# aloysius_B_v1.net
KiCad netlist of a schematic drawn in EAGLE
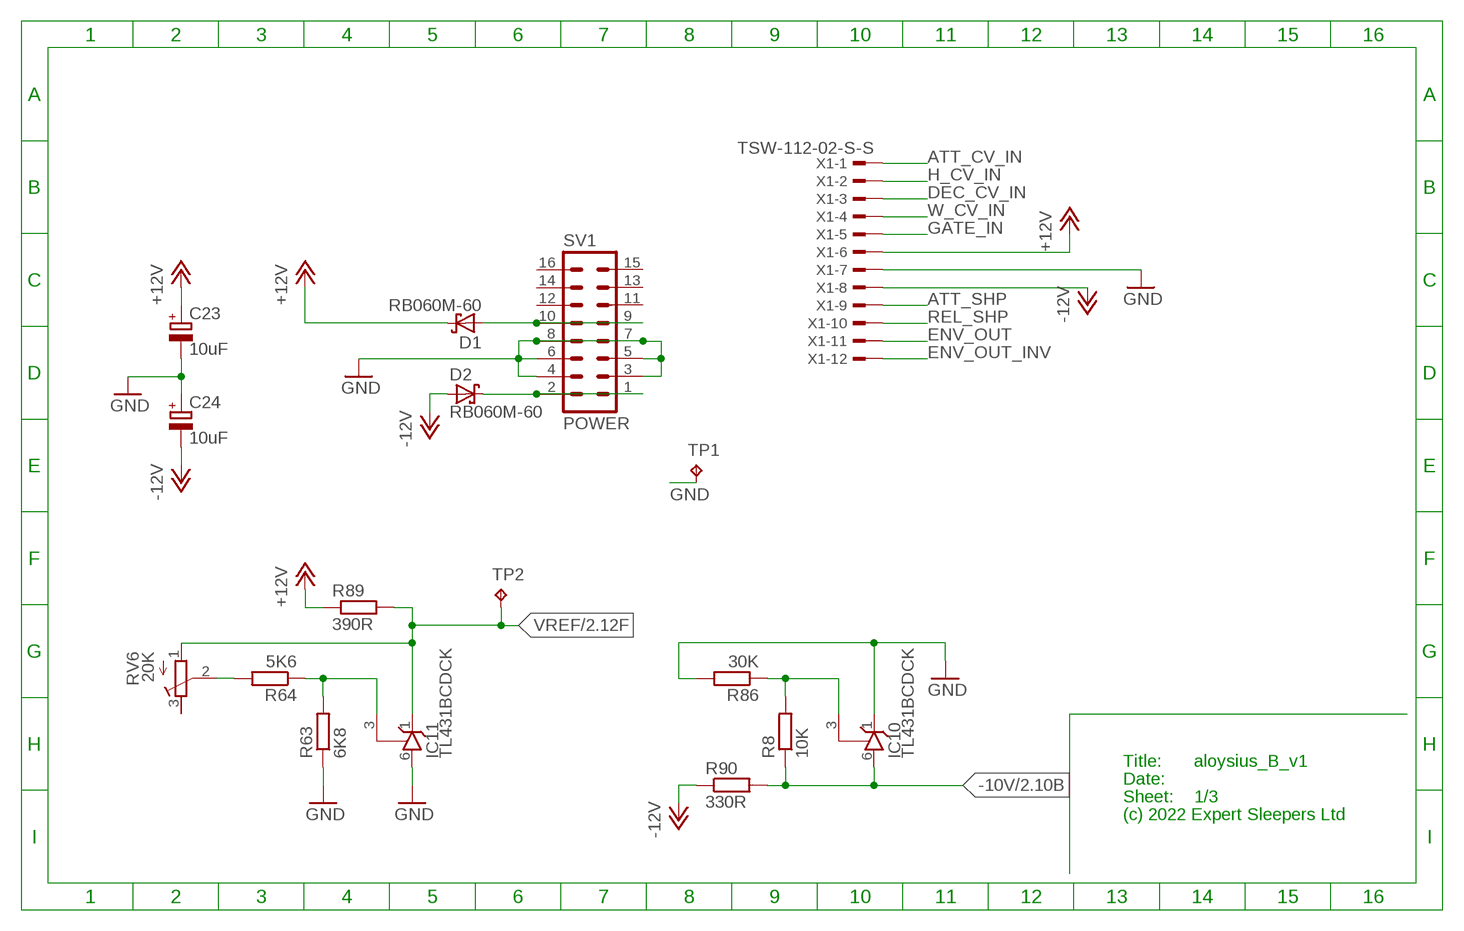
[diagram p0: schematic, sheet 1]
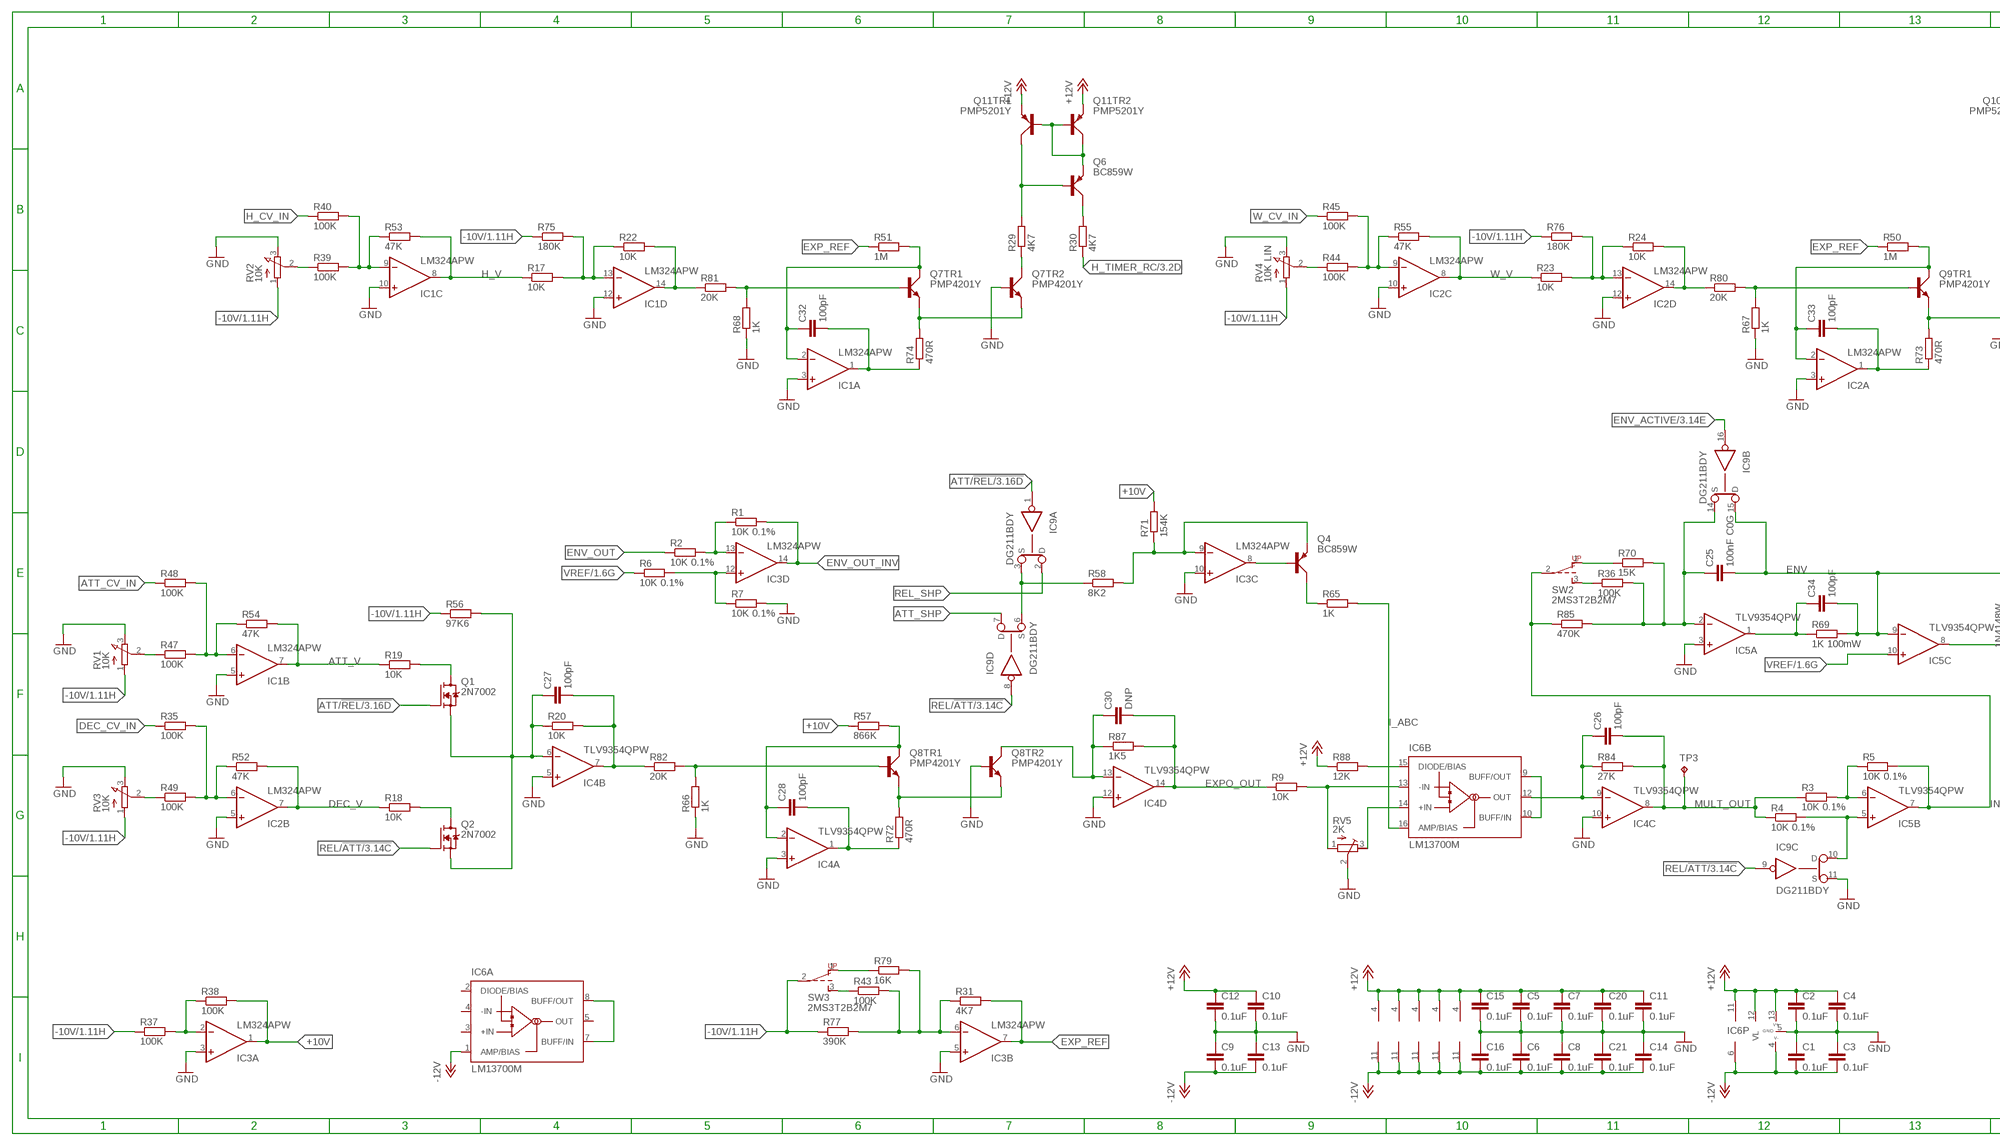
[diagram p1: schematic, sheet 2, part 1 of 2]
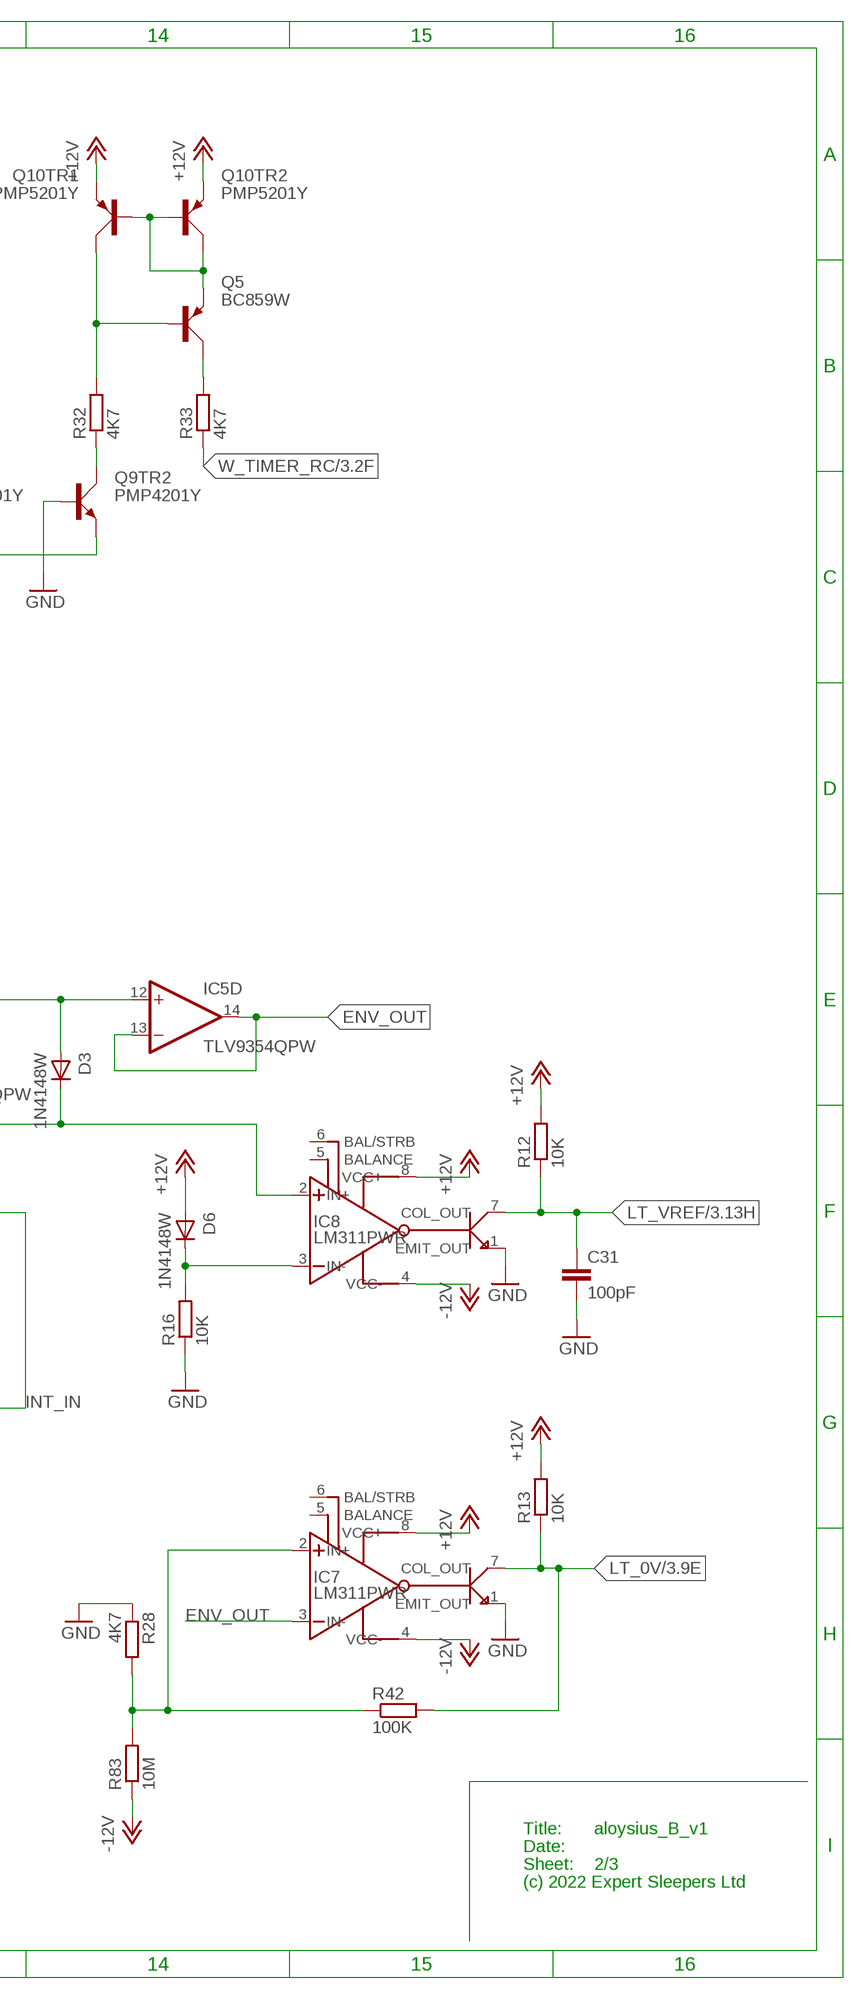
[diagram p2: schematic, sheet 2, part 2 of 2]
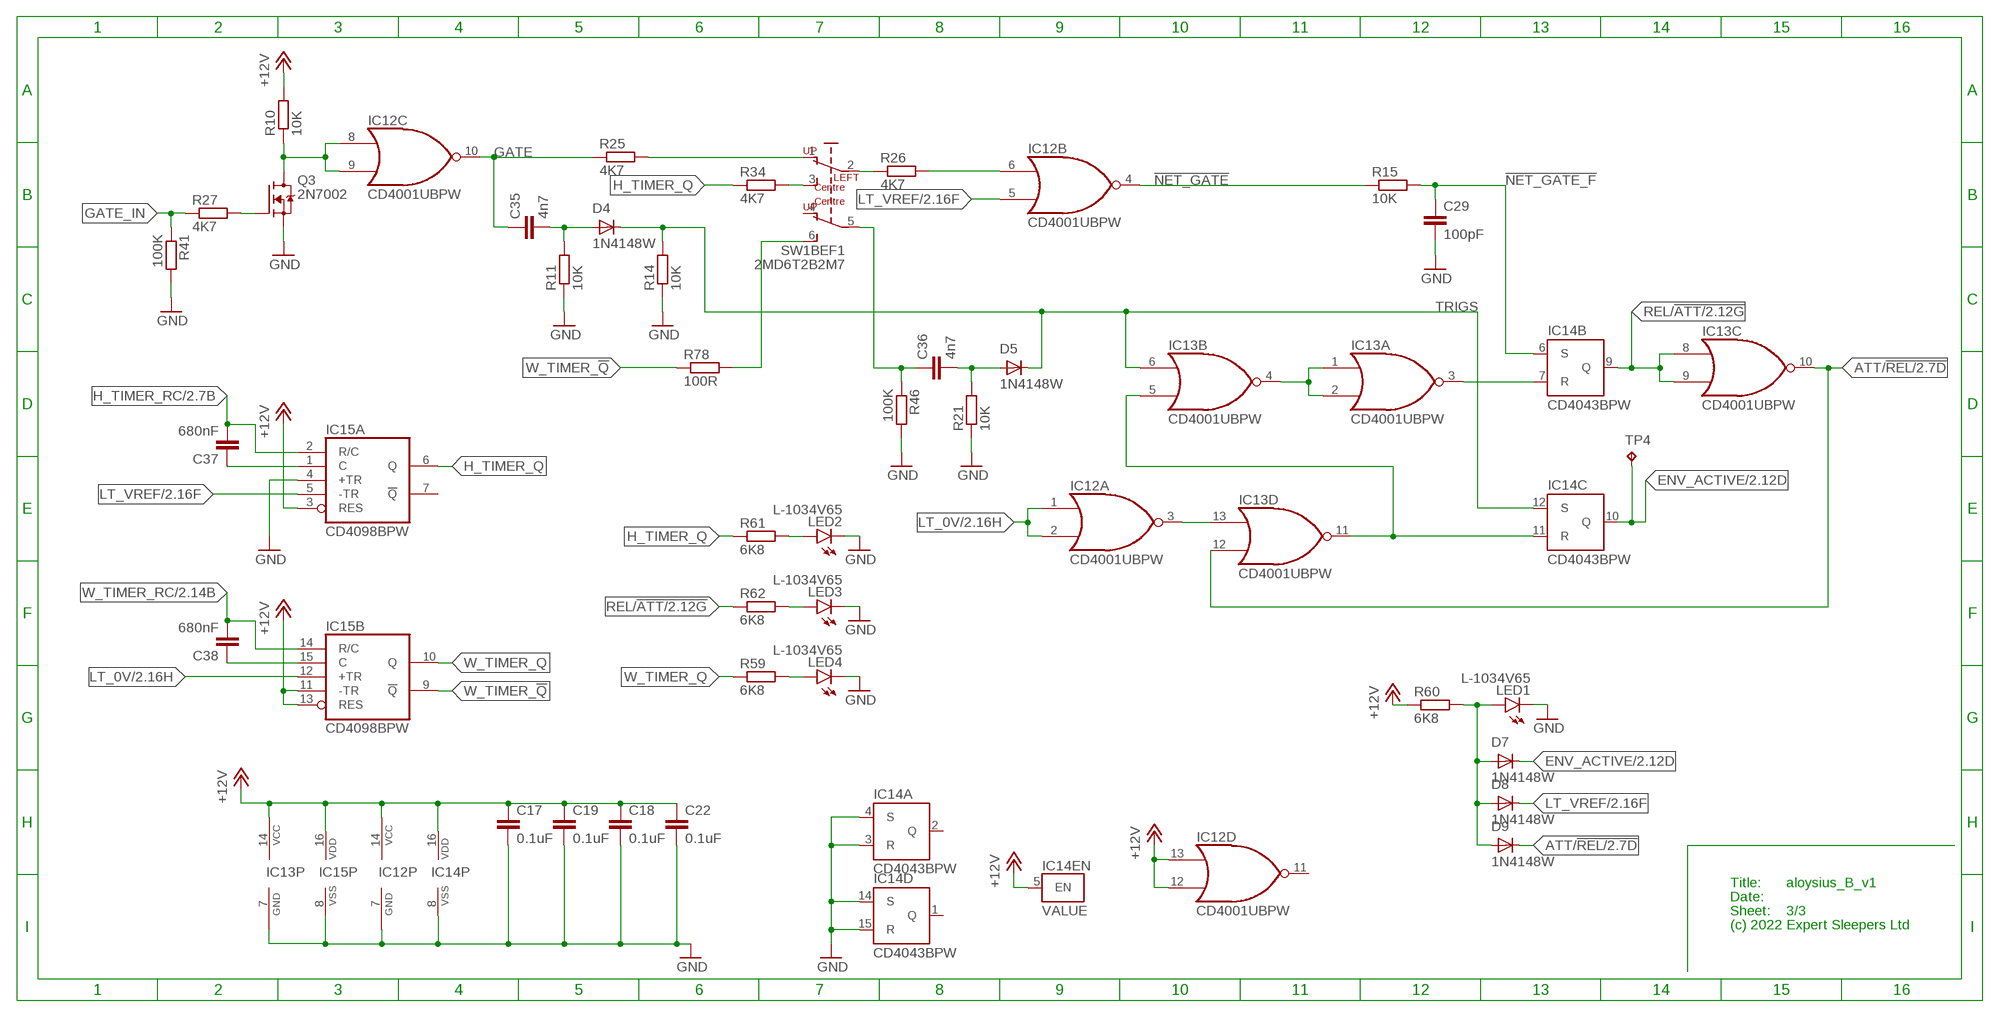
[diagram p3: schematic, sheet 3]

(export (version "E")
  (design (tool "Eeschema 10.0.6"))
  (components
    (comp (ref "C1")
      (value "0.1uF")
      (footprint "eagle-import:C0402")
      (libsource (lib "eagle-import") (part "C-EUC0402"))
    )
    (comp (ref "C2")
      (value "0.1uF")
      (footprint "eagle-import:C0402")
      (libsource (lib "eagle-import") (part "C-EUC0402"))
    )
    (comp (ref "C3")
      (value "0.1uF")
      (footprint "eagle-import:C0402")
      (libsource (lib "eagle-import") (part "C-EUC0402"))
    )
    (comp (ref "C4")
      (value "0.1uF")
      (footprint "eagle-import:C0402")
      (libsource (lib "eagle-import") (part "C-EUC0402"))
    )
    (comp (ref "C5")
      (value "0.1uF")
      (footprint "eagle-import:C0402")
      (libsource (lib "eagle-import") (part "C-EUC0402"))
    )
    (comp (ref "C6")
      (value "0.1uF")
      (footprint "eagle-import:C0402")
      (libsource (lib "eagle-import") (part "C-EUC0402"))
    )
    (comp (ref "C7")
      (value "0.1uF")
      (footprint "eagle-import:C0402")
      (libsource (lib "eagle-import") (part "C-EUC0402"))
    )
    (comp (ref "C8")
      (value "0.1uF")
      (footprint "eagle-import:C0402")
      (libsource (lib "eagle-import") (part "C-EUC0402"))
    )
    (comp (ref "C9")
      (value "0.1uF")
      (footprint "eagle-import:C0402")
      (libsource (lib "eagle-import") (part "C-EUC0402"))
    )
    (comp (ref "C10")
      (value "0.1uF")
      (footprint "eagle-import:C0402")
      (libsource (lib "eagle-import") (part "C-EUC0402"))
    )
    (comp (ref "C11")
      (value "0.1uF")
      (footprint "eagle-import:C0402")
      (libsource (lib "eagle-import") (part "C-EUC0402"))
    )
    (comp (ref "C12")
      (value "0.1uF")
      (footprint "eagle-import:C0402")
      (libsource (lib "eagle-import") (part "C-EUC0402"))
    )
    (comp (ref "C13")
      (value "0.1uF")
      (footprint "eagle-import:C0402")
      (libsource (lib "eagle-import") (part "C-EUC0402"))
    )
    (comp (ref "C14")
      (value "0.1uF")
      (footprint "eagle-import:C0402")
      (libsource (lib "eagle-import") (part "C-EUC0402"))
    )
    (comp (ref "C15")
      (value "0.1uF")
      (footprint "eagle-import:C0402")
      (libsource (lib "eagle-import") (part "C-EUC0402"))
    )
    (comp (ref "C16")
      (value "0.1uF")
      (footprint "eagle-import:C0402")
      (libsource (lib "eagle-import") (part "C-EUC0402"))
    )
    (comp (ref "C20")
      (value "0.1uF")
      (footprint "eagle-import:C0402")
      (libsource (lib "eagle-import") (part "C-EUC0402"))
    )
    (comp (ref "C21")
      (value "0.1uF")
      (footprint "eagle-import:C0402")
      (libsource (lib "eagle-import") (part "C-EUC0402"))
    )
    (comp (ref "C25")
      (value "100nF C0G")
      (footprint "eagle-import:C1206")
      (libsource (lib "eagle-import") (part "C-EUC1206"))
    )
    (comp (ref "C26")
      (value "100pF")
      (footprint "eagle-import:C0603")
      (libsource (lib "eagle-import") (part "C-EUC0603"))
    )
    (comp (ref "C27")
      (value "100pF")
      (footprint "eagle-import:C0603")
      (libsource (lib "eagle-import") (part "C-EUC0603"))
    )
    (comp (ref "C28")
      (value "100pF")
      (footprint "eagle-import:C0603")
      (libsource (lib "eagle-import") (part "C-EUC0603"))
    )
    (comp (ref "C30")
      (value "DNP")
      (footprint "eagle-import:C0603")
      (libsource (lib "eagle-import") (part "C-EUC0603"))
    )
    (comp (ref "C31")
      (value "100pF")
      (footprint "eagle-import:C0603")
      (libsource (lib "eagle-import") (part "C-EUC0603"))
    )
    (comp (ref "C32")
      (value "100pF")
      (footprint "eagle-import:C0603")
      (libsource (lib "eagle-import") (part "C-EUC0603"))
    )
    (comp (ref "C33")
      (value "100pF")
      (footprint "eagle-import:C0603")
      (libsource (lib "eagle-import") (part "C-EUC0603"))
    )
    (comp (ref "C34")
      (value "100pF")
      (footprint "eagle-import:C0603")
      (libsource (lib "eagle-import") (part "C-EUC0603"))
    )
    (comp (ref "D3")
      (value "1N4148W")
      (footprint "eagle-import:SOD123")
      (libsource (lib "eagle-import") (part "1N4148W"))
    )
    (comp (ref "D6")
      (value "1N4148W")
      (footprint "eagle-import:SOD123")
      (libsource (lib "eagle-import") (part "1N4148W"))
    )
    (comp (ref "IC1")
      (value "LM324APW")
      (footprint "eagle-import:PW_R-PDSO-G14")
      (libsource (lib "eagle-import") (part "TL074PW"))
    )
    (comp (ref "IC2")
      (value "LM324APW")
      (footprint "eagle-import:PW_R-PDSO-G14")
      (libsource (lib "eagle-import") (part "TL074PW"))
    )
    (comp (ref "IC3")
      (value "LM324APW")
      (footprint "eagle-import:PW_R-PDSO-G14")
      (libsource (lib "eagle-import") (part "TL074PW"))
    )
    (comp (ref "IC4")
      (value "TLV9354QPW")
      (footprint "eagle-import:PW_R-PDSO-G14")
      (libsource (lib "eagle-import") (part "TL074PW"))
    )
    (comp (ref "IC5")
      (value "TLV9354QPW")
      (footprint "eagle-import:PW_R-PDSO-G14")
      (libsource (lib "eagle-import") (part "TL074PW"))
    )
    (comp (ref "IC6")
      (value "LM13700M")
      (footprint "eagle-import:SO16")
      (libsource (lib "eagle-import") (part "LM13700M"))
    )
    (comp (ref "IC7")
      (value "LM311PWR")
      (footprint "eagle-import:SOP65P640X120-8N")
      (fields (field (name "MOUSER_PART_NUMBER") "595-LM311PWR"))
      (libsource (lib "eagle-import") (part "LM311PWR"))
    )
    (comp (ref "IC8")
      (value "LM311PWR")
      (footprint "eagle-import:SOP65P640X120-8N")
      (fields (field (name "MOUSER_PART_NUMBER") "595-LM311PWR"))
      (libsource (lib "eagle-import") (part "LM311PWR"))
    )
    (comp (ref "IC9")
      (value "DG211BDY")
      (footprint "eagle-import:SO16")
      (libsource (lib "eagle-import") (part "DG211CJD"))
    )
    (comp (ref "Q1")
      (value "2N7002")
      (footprint "eagle-import:SOT23")
      (libsource (lib "eagle-import") (part "2N7002"))
    )
    (comp (ref "Q2")
      (value "2N7002")
      (footprint "eagle-import:SOT23")
      (libsource (lib "eagle-import") (part "2N7002"))
    )
    (comp (ref "Q4")
      (value "BC859W")
      (footprint "eagle-import:SOT323")
      (libsource (lib "eagle-import") (part "BC859W"))
    )
    (comp (ref "Q5")
      (value "BC859W")
      (footprint "eagle-import:SOT323")
      (libsource (lib "eagle-import") (part "BC859W"))
    )
    (comp (ref "Q6")
      (value "BC859W")
      (footprint "eagle-import:SOT323")
      (libsource (lib "eagle-import") (part "BC859W"))
    )
    (comp (ref "Q7")
      (value "PMP4201Y")
      (footprint "eagle-import:SOT65P210X110-6N")
      (fields
        (field (name "ARROW_PART_NUMBER") "PMP4201Y,135")
        (field (name "MOUSER_PART_NUMBER") "771-PMP4201Y135")
      )
      (libsource (lib "eagle-import") (part "PMP4201Y"))
    )
    (comp (ref "Q8")
      (value "PMP4201Y")
      (footprint "eagle-import:SOT65P210X110-6N")
      (fields
        (field (name "ARROW_PART_NUMBER") "PMP4201Y,135")
        (field (name "MOUSER_PART_NUMBER") "771-PMP4201Y135")
      )
      (libsource (lib "eagle-import") (part "PMP4201Y"))
    )
    (comp (ref "Q9")
      (value "PMP4201Y")
      (footprint "eagle-import:SOT65P210X110-6N")
      (fields
        (field (name "ARROW_PART_NUMBER") "PMP4201Y,135")
        (field (name "MOUSER_PART_NUMBER") "771-PMP4201Y135")
      )
      (libsource (lib "eagle-import") (part "PMP4201Y"))
    )
    (comp (ref "Q10")
      (value "PMP5201Y")
      (footprint "eagle-import:SOT65P210X110-6N")
      (fields
        (field (name "ARROW_PART_NUMBER") "PMP5201Y,135")
        (field (name "MOUSER_PART_NUMBER") "771-PMP5201Y135")
      )
      (libsource (lib "eagle-import") (part "PMP5201Y"))
    )
    (comp (ref "Q11")
      (value "PMP5201Y")
      (footprint "eagle-import:SOT65P210X110-6N")
      (fields
        (field (name "ARROW_PART_NUMBER") "PMP5201Y,135")
        (field (name "MOUSER_PART_NUMBER") "771-PMP5201Y135")
      )
      (libsource (lib "eagle-import") (part "PMP5201Y"))
    )
    (comp (ref "R1")
      (value "10K 0.1%")
      (footprint "eagle-import:R0603")
      (libsource (lib "eagle-import") (part "R-EU_R0603"))
    )
    (comp (ref "R2")
      (value "10K 0.1%")
      (footprint "eagle-import:R0603")
      (libsource (lib "eagle-import") (part "R-EU_R0603"))
    )
    (comp (ref "R3")
      (value "10K 0.1%")
      (footprint "eagle-import:R0603")
      (libsource (lib "eagle-import") (part "R-EU_R0603"))
    )
    (comp (ref "R4")
      (value "10K 0.1%")
      (footprint "eagle-import:R0603")
      (libsource (lib "eagle-import") (part "R-EU_R0603"))
    )
    (comp (ref "R5")
      (value "10K 0.1%")
      (footprint "eagle-import:R0603")
      (libsource (lib "eagle-import") (part "R-EU_R0603"))
    )
    (comp (ref "R6")
      (value "10K 0.1%")
      (footprint "eagle-import:R0603")
      (libsource (lib "eagle-import") (part "R-EU_R0603"))
    )
    (comp (ref "R7")
      (value "10K 0.1%")
      (footprint "eagle-import:R0603")
      (libsource (lib "eagle-import") (part "R-EU_R0603"))
    )
    (comp (ref "R9")
      (value "10K")
      (footprint "eagle-import:R0603")
      (libsource (lib "eagle-import") (part "R-EU_R0603"))
    )
    (comp (ref "R12")
      (value "10K")
      (footprint "eagle-import:R0603")
      (libsource (lib "eagle-import") (part "R-EU_R0603"))
    )
    (comp (ref "R13")
      (value "10K")
      (footprint "eagle-import:R0603")
      (libsource (lib "eagle-import") (part "R-EU_R0603"))
    )
    (comp (ref "R16")
      (value "10K")
      (footprint "eagle-import:R0603")
      (libsource (lib "eagle-import") (part "R-EU_R0603"))
    )
    (comp (ref "R17")
      (value "10K")
      (footprint "eagle-import:R0603")
      (libsource (lib "eagle-import") (part "R-EU_R0603"))
    )
    (comp (ref "R18")
      (value "10K")
      (footprint "eagle-import:R0603")
      (libsource (lib "eagle-import") (part "R-EU_R0603"))
    )
    (comp (ref "R19")
      (value "10K")
      (footprint "eagle-import:R0603")
      (libsource (lib "eagle-import") (part "R-EU_R0603"))
    )
    (comp (ref "R20")
      (value "10K")
      (footprint "eagle-import:R0603")
      (libsource (lib "eagle-import") (part "R-EU_R0603"))
    )
    (comp (ref "R22")
      (value "10K")
      (footprint "eagle-import:R0603")
      (libsource (lib "eagle-import") (part "R-EU_R0603"))
    )
    (comp (ref "R23")
      (value "10K")
      (footprint "eagle-import:R0603")
      (libsource (lib "eagle-import") (part "R-EU_R0603"))
    )
    (comp (ref "R24")
      (value "10K")
      (footprint "eagle-import:R0603")
      (libsource (lib "eagle-import") (part "R-EU_R0603"))
    )
    (comp (ref "R28")
      (value "4K7")
      (footprint "eagle-import:R0603")
      (libsource (lib "eagle-import") (part "R-EU_R0603"))
    )
    (comp (ref "R29")
      (value "4K7")
      (footprint "eagle-import:R0603")
      (libsource (lib "eagle-import") (part "R-EU_R0603"))
    )
    (comp (ref "R30")
      (value "4K7")
      (footprint "eagle-import:R0603")
      (libsource (lib "eagle-import") (part "R-EU_R0603"))
    )
    (comp (ref "R31")
      (value "4K7")
      (footprint "eagle-import:R0603")
      (libsource (lib "eagle-import") (part "R-EU_R0603"))
    )
    (comp (ref "R32")
      (value "4K7")
      (footprint "eagle-import:R0603")
      (libsource (lib "eagle-import") (part "R-EU_R0603"))
    )
    (comp (ref "R33")
      (value "4K7")
      (footprint "eagle-import:R0603")
      (libsource (lib "eagle-import") (part "R-EU_R0603"))
    )
    (comp (ref "R35")
      (value "100K")
      (footprint "eagle-import:R0603")
      (libsource (lib "eagle-import") (part "R-EU_R0603"))
    )
    (comp (ref "R36")
      (value "100K")
      (footprint "eagle-import:R0603")
      (libsource (lib "eagle-import") (part "R-EU_R0603"))
    )
    (comp (ref "R37")
      (value "100K")
      (footprint "eagle-import:R0603")
      (libsource (lib "eagle-import") (part "R-EU_R0603"))
    )
    (comp (ref "R38")
      (value "100K")
      (footprint "eagle-import:R0603")
      (libsource (lib "eagle-import") (part "R-EU_R0603"))
    )
    (comp (ref "R39")
      (value "100K")
      (footprint "eagle-import:R0603")
      (libsource (lib "eagle-import") (part "R-EU_R0603"))
    )
    (comp (ref "R40")
      (value "100K")
      (footprint "eagle-import:R0603")
      (libsource (lib "eagle-import") (part "R-EU_R0603"))
    )
    (comp (ref "R42")
      (value "100K")
      (footprint "eagle-import:R0603")
      (libsource (lib "eagle-import") (part "R-EU_R0603"))
    )
    (comp (ref "R43")
      (value "100K")
      (footprint "eagle-import:R0603")
      (libsource (lib "eagle-import") (part "R-EU_R0603"))
    )
    (comp (ref "R44")
      (value "100K")
      (footprint "eagle-import:R0603")
      (libsource (lib "eagle-import") (part "R-EU_R0603"))
    )
    (comp (ref "R45")
      (value "100K")
      (footprint "eagle-import:R0603")
      (libsource (lib "eagle-import") (part "R-EU_R0603"))
    )
    (comp (ref "R47")
      (value "100K")
      (footprint "eagle-import:R0603")
      (libsource (lib "eagle-import") (part "R-EU_R0603"))
    )
    (comp (ref "R48")
      (value "100K")
      (footprint "eagle-import:R0603")
      (libsource (lib "eagle-import") (part "R-EU_R0603"))
    )
    (comp (ref "R49")
      (value "100K")
      (footprint "eagle-import:R0603")
      (libsource (lib "eagle-import") (part "R-EU_R0603"))
    )
    (comp (ref "R50")
      (value "1M")
      (footprint "eagle-import:R0603")
      (libsource (lib "eagle-import") (part "R-EU_R0603"))
    )
    (comp (ref "R51")
      (value "1M")
      (footprint "eagle-import:R0603")
      (libsource (lib "eagle-import") (part "R-EU_R0603"))
    )
    (comp (ref "R52")
      (value "47K")
      (footprint "eagle-import:R0603")
      (libsource (lib "eagle-import") (part "R-EU_R0603"))
    )
    (comp (ref "R53")
      (value "47K")
      (footprint "eagle-import:R0603")
      (libsource (lib "eagle-import") (part "R-EU_R0603"))
    )
    (comp (ref "R54")
      (value "47K")
      (footprint "eagle-import:R0603")
      (libsource (lib "eagle-import") (part "R-EU_R0603"))
    )
    (comp (ref "R55")
      (value "47K")
      (footprint "eagle-import:R0603")
      (libsource (lib "eagle-import") (part "R-EU_R0603"))
    )
    (comp (ref "R56")
      (value "97K6")
      (footprint "eagle-import:R0603")
      (libsource (lib "eagle-import") (part "R-EU_R0603"))
    )
    (comp (ref "R57")
      (value "866K")
      (footprint "eagle-import:R0603")
      (libsource (lib "eagle-import") (part "R-EU_R0603"))
    )
    (comp (ref "R58")
      (value "8K2")
      (footprint "eagle-import:R0603")
      (libsource (lib "eagle-import") (part "R-EU_R0603"))
    )
    (comp (ref "R65")
      (value "1K")
      (footprint "eagle-import:R0603")
      (libsource (lib "eagle-import") (part "R-EU_R0603"))
    )
    (comp (ref "R66")
      (value "1K")
      (footprint "eagle-import:R0603")
      (libsource (lib "eagle-import") (part "R-EU_R0603"))
    )
    (comp (ref "R67")
      (value "1K")
      (footprint "eagle-import:R0603")
      (libsource (lib "eagle-import") (part "R-EU_R0603"))
    )
    (comp (ref "R68")
      (value "1K")
      (footprint "eagle-import:R0603")
      (libsource (lib "eagle-import") (part "R-EU_R0603"))
    )
    (comp (ref "R69")
      (value "1K 100mW")
      (footprint "eagle-import:R0603")
      (libsource (lib "eagle-import") (part "R-EU_R0603"))
    )
    (comp (ref "R70")
      (value "15K")
      (footprint "eagle-import:R0603")
      (libsource (lib "eagle-import") (part "R-EU_R0603"))
    )
    (comp (ref "R71")
      (value "154K")
      (footprint "eagle-import:R0603")
      (libsource (lib "eagle-import") (part "R-EU_R0603"))
    )
    (comp (ref "R72")
      (value "470R")
      (footprint "eagle-import:R0603")
      (libsource (lib "eagle-import") (part "R-EU_R0603"))
    )
    (comp (ref "R73")
      (value "470R")
      (footprint "eagle-import:R0603")
      (libsource (lib "eagle-import") (part "R-EU_R0603"))
    )
    (comp (ref "R74")
      (value "470R")
      (footprint "eagle-import:R0603")
      (libsource (lib "eagle-import") (part "R-EU_R0603"))
    )
    (comp (ref "R75")
      (value "180K")
      (footprint "eagle-import:R0603")
      (libsource (lib "eagle-import") (part "R-EU_R0603"))
    )
    (comp (ref "R76")
      (value "180K")
      (footprint "eagle-import:R0603")
      (libsource (lib "eagle-import") (part "R-EU_R0603"))
    )
    (comp (ref "R77")
      (value "390K")
      (footprint "eagle-import:R0603")
      (libsource (lib "eagle-import") (part "R-EU_R0603"))
    )
    (comp (ref "R79")
      (value "16K")
      (footprint "eagle-import:R0603")
      (libsource (lib "eagle-import") (part "R-EU_R0603"))
    )
    (comp (ref "R80")
      (value "20K")
      (footprint "eagle-import:R0603")
      (libsource (lib "eagle-import") (part "R-EU_R0603"))
    )
    (comp (ref "R81")
      (value "20K")
      (footprint "eagle-import:R0603")
      (libsource (lib "eagle-import") (part "R-EU_R0603"))
    )
    (comp (ref "R82")
      (value "20K")
      (footprint "eagle-import:R0603")
      (libsource (lib "eagle-import") (part "R-EU_R0603"))
    )
    (comp (ref "R83")
      (value "10M")
      (footprint "eagle-import:R0603")
      (libsource (lib "eagle-import") (part "R-EU_R0603"))
    )
    (comp (ref "R84")
      (value "27K")
      (footprint "eagle-import:R0603")
      (libsource (lib "eagle-import") (part "R-EU_R0603"))
    )
    (comp (ref "R85")
      (value "470K")
      (footprint "eagle-import:R0603")
      (libsource (lib "eagle-import") (part "R-EU_R0603"))
    )
    (comp (ref "R87")
      (value "1K5")
      (footprint "eagle-import:R0603")
      (libsource (lib "eagle-import") (part "R-EU_R0603"))
    )
    (comp (ref "R88")
      (value "12K")
      (footprint "eagle-import:R0603")
      (libsource (lib "eagle-import") (part "R-EU_R0603"))
    )
    (comp (ref "RV1")
      (value "10K")
      (footprint "eagle-import:RD1610NOA0X")
      (libsource (lib "eagle-import") (part "RD1610NOA0X"))
    )
    (comp (ref "RV2")
      (value "10K")
      (footprint "eagle-import:RD1610NOA0X")
      (libsource (lib "eagle-import") (part "RD1610NOA0X"))
    )
    (comp (ref "RV3")
      (value "10K")
      (footprint "eagle-import:RD1610NOA0X")
      (libsource (lib "eagle-import") (part "RD1610NOA0X"))
    )
    (comp (ref "RV4")
      (value "10K LIN")
      (footprint "eagle-import:RD1610NOA0X")
      (libsource (lib "eagle-import") (part "RD1610NOA0X"))
    )
    (comp (ref "RV5")
      (value "2K")
      (footprint "eagle-import:RTRIM3296W")
      (libsource (lib "eagle-import") (part "T93YA"))
    )
    (comp (ref "SW2")
      (value "2MS3T2B2M7")
      (footprint "eagle-import:2MS1T2B2M7RE")
      (libsource (lib "eagle-import") (part "2MS3M7T2B2"))
    )
    (comp (ref "SW3")
      (value "2MS3T2B2M7")
      (footprint "eagle-import:2MS1T2B2M7RE")
      (libsource (lib "eagle-import") (part "2MS3M7T2B2"))
    )
    (comp (ref "TP3")
      (value "RA2")
      (footprint "eagle-import:P1-13")
      (libsource (lib "eagle-import") (part "TPPAD1-13"))
    )
    (comp (ref "C17")
      (value "0.1uF")
      (footprint "eagle-import:C0402")
      (libsource (lib "eagle-import") (part "C-EUC0402"))
    )
    (comp (ref "C18")
      (value "0.1uF")
      (footprint "eagle-import:C0402")
      (libsource (lib "eagle-import") (part "C-EUC0402"))
    )
    (comp (ref "C19")
      (value "0.1uF")
      (footprint "eagle-import:C0402")
      (libsource (lib "eagle-import") (part "C-EUC0402"))
    )
    (comp (ref "C22")
      (value "0.1uF")
      (footprint "eagle-import:C0402")
      (libsource (lib "eagle-import") (part "C-EUC0402"))
    )
    (comp (ref "C29")
      (value "100pF")
      (footprint "eagle-import:C0603")
      (libsource (lib "eagle-import") (part "C-EUC0603"))
    )
    (comp (ref "C35")
      (value "4n7")
      (footprint "eagle-import:C0603")
      (libsource (lib "eagle-import") (part "C-EUC0603"))
    )
    (comp (ref "C36")
      (value "4n7")
      (footprint "eagle-import:C0603")
      (libsource (lib "eagle-import") (part "C-EUC0603"))
    )
    (comp (ref "C37")
      (value "680nF")
      (footprint "eagle-import:C0603")
      (libsource (lib "eagle-import") (part "C-EUC0603"))
    )
    (comp (ref "C38")
      (value "680nF")
      (footprint "eagle-import:C0603")
      (libsource (lib "eagle-import") (part "C-EUC0603"))
    )
    (comp (ref "D4")
      (value "1N4148W")
      (footprint "eagle-import:SOD123")
      (libsource (lib "eagle-import") (part "1N4148W"))
    )
    (comp (ref "D5")
      (value "1N4148W")
      (footprint "eagle-import:SOD123")
      (libsource (lib "eagle-import") (part "1N4148W"))
    )
    (comp (ref "D7")
      (value "1N4148W")
      (footprint "eagle-import:SOD123")
      (libsource (lib "eagle-import") (part "1N4148W"))
    )
    (comp (ref "D8")
      (value "1N4148W")
      (footprint "eagle-import:SOD123")
      (libsource (lib "eagle-import") (part "1N4148W"))
    )
    (comp (ref "D9")
      (value "1N4148W")
      (footprint "eagle-import:SOD123")
      (libsource (lib "eagle-import") (part "1N4148W"))
    )
    (comp (ref "IC12")
      (value "CD4001UBPW")
      (footprint "eagle-import:TSSOP14")
      (libsource (lib "eagle-import") (part "CD4001UBPW"))
    )
    (comp (ref "IC13")
      (value "CD4001UBPW")
      (footprint "eagle-import:TSSOP14")
      (libsource (lib "eagle-import") (part "CD4001UBPW"))
    )
    (comp (ref "IC14")
      (value "CD4043BPW")
      (footprint "eagle-import:TSSOP16")
      (libsource (lib "eagle-import") (part "CD4043BPW"))
    )
    (comp (ref "IC15")
      (value "CD4098BPW")
      (footprint "eagle-import:TSSOP16")
      (libsource (lib "eagle-import") (part "CD4098BPW"))
    )
    (comp (ref "LED1")
      (value "L-1034V65")
      (footprint "eagle-import:L-1034_V6.5MM")
      (libsource (lib "eagle-import") (part "L-1034V65"))
    )
    (comp (ref "LED2")
      (value "L-1034V65")
      (footprint "eagle-import:L-1034_V6.5MM")
      (libsource (lib "eagle-import") (part "L-1034V65"))
    )
    (comp (ref "LED3")
      (value "L-1034V65")
      (footprint "eagle-import:L-1034_V6.5MM")
      (libsource (lib "eagle-import") (part "L-1034V65"))
    )
    (comp (ref "LED4")
      (value "L-1034V65")
      (footprint "eagle-import:L-1034_V6.5MM")
      (libsource (lib "eagle-import") (part "L-1034V65"))
    )
    (comp (ref "Q3")
      (value "2N7002")
      (footprint "eagle-import:SOT23")
      (libsource (lib "eagle-import") (part "2N7002"))
    )
    (comp (ref "R10")
      (value "10K")
      (footprint "eagle-import:R0603")
      (libsource (lib "eagle-import") (part "R-EU_R0603"))
    )
    (comp (ref "R11")
      (value "10K")
      (footprint "eagle-import:R0603")
      (libsource (lib "eagle-import") (part "R-EU_R0603"))
    )
    (comp (ref "R14")
      (value "10K")
      (footprint "eagle-import:R0603")
      (libsource (lib "eagle-import") (part "R-EU_R0603"))
    )
    (comp (ref "R15")
      (value "10K")
      (footprint "eagle-import:R0603")
      (libsource (lib "eagle-import") (part "R-EU_R0603"))
    )
    (comp (ref "R21")
      (value "10K")
      (footprint "eagle-import:R0603")
      (libsource (lib "eagle-import") (part "R-EU_R0603"))
    )
    (comp (ref "R25")
      (value "4K7")
      (footprint "eagle-import:R0603")
      (libsource (lib "eagle-import") (part "R-EU_R0603"))
    )
    (comp (ref "R26")
      (value "4K7")
      (footprint "eagle-import:R0603")
      (libsource (lib "eagle-import") (part "R-EU_R0603"))
    )
    (comp (ref "R27")
      (value "4K7")
      (footprint "eagle-import:R0603")
      (libsource (lib "eagle-import") (part "R-EU_R0603"))
    )
    (comp (ref "R34")
      (value "4K7")
      (footprint "eagle-import:R0603")
      (libsource (lib "eagle-import") (part "R-EU_R0603"))
    )
    (comp (ref "R41")
      (value "100K")
      (footprint "eagle-import:R0603")
      (libsource (lib "eagle-import") (part "R-EU_R0603"))
    )
    (comp (ref "R46")
      (value "100K")
      (footprint "eagle-import:R0603")
      (libsource (lib "eagle-import") (part "R-EU_R0603"))
    )
    (comp (ref "R59")
      (value "6K8")
      (footprint "eagle-import:R0603")
      (libsource (lib "eagle-import") (part "R-EU_R0603"))
    )
    (comp (ref "R60")
      (value "6K8")
      (footprint "eagle-import:R0603")
      (libsource (lib "eagle-import") (part "R-EU_R0603"))
    )
    (comp (ref "R61")
      (value "6K8")
      (footprint "eagle-import:R0603")
      (libsource (lib "eagle-import") (part "R-EU_R0603"))
    )
    (comp (ref "R62")
      (value "6K8")
      (footprint "eagle-import:R0603")
      (libsource (lib "eagle-import") (part "R-EU_R0603"))
    )
    (comp (ref "R78")
      (value "100R")
      (footprint "eagle-import:R0603")
      (libsource (lib "eagle-import") (part "R-EU_R0603"))
    )
    (comp (ref "SW1")
      (value "2MD6T2B2M7")
      (footprint "eagle-import:2MD1T2B2M7RE")
      (libsource (lib "eagle-import") (part "2MD6M7T2B2"))
    )
    (comp (ref "TP4")
      (value "RA2")
      (footprint "eagle-import:P1-13")
      (libsource (lib "eagle-import") (part "TPPAD1-13"))
    )
    (comp (ref "C23")
      (value "10uF")
      (footprint "eagle-import:UD-4X5,8_NICHICON")
      (libsource (lib "eagle-import") (part "CPOL-EUUD-4X5,8"))
    )
    (comp (ref "C24")
      (value "10uF")
      (footprint "eagle-import:UD-4X5,8_NICHICON")
      (libsource (lib "eagle-import") (part "CPOL-EUUD-4X5,8"))
    )
    (comp (ref "D1")
      (value "RB060M-60")
      (footprint "eagle-import:SOD123FL")
      (libsource (lib "eagle-import") (part "RB060M-60"))
    )
    (comp (ref "D2")
      (value "RB060M-60")
      (footprint "eagle-import:SOD123FL")
      (libsource (lib "eagle-import") (part "RB060M-60"))
    )
    (comp (ref "IC10")
      (value "TL431BCDCK")
      (footprint "eagle-import:DCK_SC-70")
      (libsource (lib "eagle-import") (part "TL431DCKBC"))
    )
    (comp (ref "IC11")
      (value "TL431BCDCK")
      (footprint "eagle-import:DCK_SC-70")
      (libsource (lib "eagle-import") (part "TL431DCKBC"))
    )
    (comp (ref "R8")
      (value "10K")
      (footprint "eagle-import:R0603")
      (libsource (lib "eagle-import") (part "R-EU_R0603"))
    )
    (comp (ref "R63")
      (value "6K8")
      (footprint "eagle-import:R0603")
      (libsource (lib "eagle-import") (part "R-EU_R0603"))
    )
    (comp (ref "R64")
      (value "5K6")
      (footprint "eagle-import:R0603")
      (libsource (lib "eagle-import") (part "R-EU_R0603"))
    )
    (comp (ref "R86")
      (value "30K")
      (footprint "eagle-import:R0603")
      (libsource (lib "eagle-import") (part "R-EU_R0603"))
    )
    (comp (ref "R89")
      (value "390R")
      (footprint "eagle-import:R1206")
      (libsource (lib "eagle-import") (part "R-EU_R1206"))
    )
    (comp (ref "R90")
      (value "330R")
      (footprint "eagle-import:R1206")
      (libsource (lib "eagle-import") (part "R-EU_R1206"))
    )
    (comp (ref "RV6")
      (value "20K")
      (footprint "eagle-import:TC33X")
      (libsource (lib "eagle-import") (part "TC33X"))
    )
    (comp (ref "SV1")
      (value "POWER")
      (footprint "eagle-import:ML16")
      (libsource (lib "eagle-import") (part "ML16"))
    )
    (comp (ref "TP1")
      (value "RA2")
      (footprint "eagle-import:P1-13")
      (libsource (lib "eagle-import") (part "TPPAD1-13"))
    )
    (comp (ref "TP2")
      (value "RA2")
      (footprint "eagle-import:P1-13")
      (libsource (lib "eagle-import") (part "TPPAD1-13"))
    )
    (comp (ref "X1")
      (value "TSW-112-02-S-S")
      (footprint "eagle-import:TSW-112-02-S-S")
      (libsource (lib "eagle-import") (part "TSW-112-02-S-S"))
    )
  )
  (nets
    (net (code "1") (name "+10V") (class "Default")
      (node (ref "IC3") (pin "1") (pinfunction "OUT_1") (pintype "output"))
      (node (ref "R38") (pin "2") (pinfunction "2_2") (pintype "passive"))
      (node (ref "R57") (pin "1") (pinfunction "1_1") (pintype "passive"))
      (node (ref "R71") (pin "2") (pinfunction "2_2") (pintype "passive"))
    )
    (net (code "2") (name "+12V") (class "Default")
      (node (ref "C10") (pin "1") (pinfunction "1_1") (pintype "passive"))
      (node (ref "C11") (pin "1") (pinfunction "1_1") (pintype "passive"))
      (node (ref "C12") (pin "1") (pinfunction "1_1") (pintype "passive"))
      (node (ref "C15") (pin "1") (pinfunction "1_1") (pintype "passive"))
      (node (ref "C17") (pin "1") (pinfunction "1_1") (pintype "passive"))
      (node (ref "C18") (pin "1") (pinfunction "1_1") (pintype "passive"))
      (node (ref "C19") (pin "1") (pinfunction "1_1") (pintype "passive"))
      (node (ref "C2") (pin "1") (pinfunction "1_1") (pintype "passive"))
      (node (ref "C20") (pin "1") (pinfunction "1_1") (pintype "passive"))
      (node (ref "C22") (pin "1") (pinfunction "1_1") (pintype "passive"))
      (node (ref "C23") (pin "+") (pinfunction "+_+") (pintype "passive"))
      (node (ref "C4") (pin "1") (pinfunction "1_1") (pintype "passive"))
      (node (ref "C5") (pin "1") (pinfunction "1_1") (pintype "passive"))
      (node (ref "C7") (pin "1") (pinfunction "1_1") (pintype "passive"))
      (node (ref "D1") (pin "C") (pinfunction "C_C") (pintype "passive"))
      (node (ref "D6") (pin "A") (pinfunction "A_A") (pintype "passive"))
      (node (ref "IC1") (pin "4") (pinfunction "V+_4") (pintype "power_in"))
      (node (ref "IC12") (pin "12") (pinfunction "I1_12") (pintype "input"))
      (node (ref "IC12") (pin "13") (pinfunction "I0_13") (pintype "input"))
      (node (ref "IC12") (pin "14") (pinfunction "VCC_14") (pintype "power_in"))
      (node (ref "IC13") (pin "14") (pinfunction "VCC_14") (pintype "power_in"))
      (node (ref "IC14") (pin "16") (pinfunction "VDD_16") (pintype "power_in"))
      (node (ref "IC14") (pin "5") (pinfunction "EN_5") (pintype "input"))
      (node (ref "IC15") (pin "11") (pinfunction "-TR_11") (pintype "input"))
      (node (ref "IC15") (pin "13") (pinfunction "RES_13") (pintype "input"))
      (node (ref "IC15") (pin "16") (pinfunction "VDD_16") (pintype "power_in"))
      (node (ref "IC15") (pin "3") (pinfunction "RES_3") (pintype "input"))
      (node (ref "IC2") (pin "4") (pinfunction "V+_4") (pintype "power_in"))
      (node (ref "IC3") (pin "4") (pinfunction "V+_4") (pintype "power_in"))
      (node (ref "IC4") (pin "4") (pinfunction "V+_4") (pintype "power_in"))
      (node (ref "IC5") (pin "4") (pinfunction "V+_4") (pintype "power_in"))
      (node (ref "IC6") (pin "11") (pinfunction "V+_11") (pintype "power_in"))
      (node (ref "IC7") (pin "8") (pinfunction "VCC+_8") (pintype "power_in"))
      (node (ref "IC8") (pin "8") (pinfunction "VCC+_8") (pintype "power_in"))
      (node (ref "IC9") (pin "12") (pinfunction "VL_12") (pintype "input"))
      (node (ref "IC9") (pin "13") (pinfunction "V+_13") (pintype "power_in"))
      (node (ref "Q10") (pin "4") (pinfunction "E_4") (pintype "passive"))
      (node (ref "Q10") (pin "5") (pinfunction "E_5") (pintype "passive"))
      (node (ref "Q11") (pin "4") (pinfunction "E_4") (pintype "passive"))
      (node (ref "Q11") (pin "5") (pinfunction "E_5") (pintype "passive"))
      (node (ref "R10") (pin "2") (pinfunction "2_2") (pintype "passive"))
      (node (ref "R12") (pin "2") (pinfunction "2_2") (pintype "passive"))
      (node (ref "R13") (pin "2") (pinfunction "2_2") (pintype "passive"))
      (node (ref "R60") (pin "1") (pinfunction "1_1") (pintype "passive"))
      (node (ref "R88") (pin "1") (pinfunction "1_1") (pintype "passive"))
      (node (ref "R89") (pin "1") (pinfunction "1_1") (pintype "passive"))
      (node (ref "X1") (pin "6") (pinfunction "1_6") (pintype "passive"))
    )
    (net (code "3") (name "-10V") (class "Default")
      (node (ref "IC10") (pin "6") (pinfunction "A_6") (pintype "passive"))
      (node (ref "R37") (pin "1") (pinfunction "1_1") (pintype "passive"))
      (node (ref "R56") (pin "1") (pinfunction "1_1") (pintype "passive"))
      (node (ref "R75") (pin "1") (pinfunction "1_1") (pintype "passive"))
      (node (ref "R76") (pin "1") (pinfunction "1_1") (pintype "passive"))
      (node (ref "R77") (pin "1") (pinfunction "1_1") (pintype "passive"))
      (node (ref "R8") (pin "1") (pinfunction "1_1") (pintype "passive"))
      (node (ref "R90") (pin "2") (pinfunction "2_2") (pintype "passive"))
      (node (ref "RV1") (pin "1") (pinfunction "A_1") (pintype "passive"))
      (node (ref "RV2") (pin "1") (pinfunction "A_1") (pintype "passive"))
      (node (ref "RV3") (pin "1") (pinfunction "A_1") (pintype "passive"))
      (node (ref "RV4") (pin "1") (pinfunction "A_1") (pintype "passive"))
      (node (ref "SW3") (pin "2") (pinfunction "PR_2") (pintype "passive"))
    )
    (net (code "4") (name "-12V") (class "Default")
      (node (ref "C1") (pin "2") (pinfunction "2_2") (pintype "passive"))
      (node (ref "C13") (pin "2") (pinfunction "2_2") (pintype "passive"))
      (node (ref "C14") (pin "2") (pinfunction "2_2") (pintype "passive"))
      (node (ref "C16") (pin "2") (pinfunction "2_2") (pintype "passive"))
      (node (ref "C21") (pin "2") (pinfunction "2_2") (pintype "passive"))
      (node (ref "C24") (pin "-") (pinfunction "-_-") (pintype "passive"))
      (node (ref "C3") (pin "2") (pinfunction "2_2") (pintype "passive"))
      (node (ref "C6") (pin "2") (pinfunction "2_2") (pintype "passive"))
      (node (ref "C8") (pin "2") (pinfunction "2_2") (pintype "passive"))
      (node (ref "C9") (pin "2") (pinfunction "2_2") (pintype "passive"))
      (node (ref "D2") (pin "A") (pinfunction "A_A") (pintype "passive"))
      (node (ref "IC1") (pin "11") (pinfunction "V-_11") (pintype "power_in"))
      (node (ref "IC2") (pin "11") (pinfunction "V-_11") (pintype "power_in"))
      (node (ref "IC3") (pin "11") (pinfunction "V-_11") (pintype "power_in"))
      (node (ref "IC4") (pin "11") (pinfunction "V-_11") (pintype "power_in"))
      (node (ref "IC5") (pin "11") (pinfunction "V-_11") (pintype "power_in"))
      (node (ref "IC6") (pin "1") (pinfunction "AMP/BIAS_1") (pintype "passive"))
      (node (ref "IC6") (pin "6") (pinfunction "V-_6") (pintype "power_in"))
      (node (ref "IC7") (pin "4") (pinfunction "VCC-_4") (pintype "power_in"))
      (node (ref "IC8") (pin "4") (pinfunction "VCC-_4") (pintype "power_in"))
      (node (ref "IC9") (pin "4") (pinfunction "V-_4") (pintype "power_in"))
      (node (ref "R83") (pin "1") (pinfunction "1_1") (pintype "passive"))
      (node (ref "R90") (pin "1") (pinfunction "1_1") (pintype "passive"))
      (node (ref "X1") (pin "8") (pinfunction "1_8") (pintype "passive"))
    )
    (net (code "5") (name "ATT_CV_IN") (class "Default")
      (node (ref "R48") (pin "1") (pinfunction "1_1") (pintype "passive"))
      (node (ref "X1") (pin "1") (pinfunction "1_1") (pintype "passive"))
    )
    (net (code "6") (name "ATT_SHP") (class "Default")
      (node (ref "IC9") (pin "7") (pinfunction "D_7") (pintype "bidirectional"))
      (node (ref "X1") (pin "9") (pinfunction "1_9") (pintype "passive"))
    )
    (net (code "7") (name "ATT_V") (class "Default")
      (node (ref "IC1") (pin "7") (pinfunction "OUT_7") (pintype "output"))
      (node (ref "R19") (pin "1") (pinfunction "1_1") (pintype "passive"))
      (node (ref "R54") (pin "2") (pinfunction "2_2") (pintype "passive"))
    )
    (net (code "8") (name "ATT{slash}~{REL}") (class "Default")
      (node (ref "D9") (pin "C") (pinfunction "C_C") (pintype "passive"))
      (node (ref "IC13") (pin "10") (pinfunction "O_10") (pintype "output"))
      (node (ref "IC13") (pin "12") (pinfunction "I1_12") (pintype "input"))
      (node (ref "IC9") (pin "1") (pinfunction "IN_1") (pintype "input"))
      (node (ref "Q1") (pin "1") (pinfunction "G_1") (pintype "passive"))
    )
    (net (code "9") (name "DEC_CV_IN") (class "Default")
      (node (ref "R35") (pin "1") (pinfunction "1_1") (pintype "passive"))
      (node (ref "X1") (pin "3") (pinfunction "1_3") (pintype "passive"))
    )
    (net (code "10") (name "DEC_V") (class "Default")
      (node (ref "IC2") (pin "7") (pinfunction "OUT_7") (pintype "output"))
      (node (ref "R18") (pin "1") (pinfunction "1_1") (pintype "passive"))
      (node (ref "R52") (pin "2") (pinfunction "2_2") (pintype "passive"))
    )
    (net (code "11") (name "ENV") (class "Default")
      (node (ref "C25") (pin "2") (pinfunction "2_2") (pintype "passive"))
      (node (ref "C34") (pin "2") (pinfunction "2_2") (pintype "passive"))
      (node (ref "D3") (pin "A") (pinfunction "A_A") (pintype "passive"))
      (node (ref "IC5") (pin "12") (pinfunction "+IN_12") (pintype "input"))
      (node (ref "IC5") (pin "9") (pinfunction "-IN_9") (pintype "input"))
      (node (ref "IC9") (pin "15") (pinfunction "D_15") (pintype "bidirectional"))
      (node (ref "R69") (pin "2") (pinfunction "2_2") (pintype "passive"))
    )
    (net (code "12") (name "ENV_ACTIVE") (class "Default")
      (node (ref "D7") (pin "C") (pinfunction "C_C") (pintype "passive"))
      (node (ref "IC14") (pin "10") (pinfunction "Q_10") (pintype "output"))
      (node (ref "IC9") (pin "16") (pinfunction "IN_16") (pintype "input"))
      (node (ref "TP4") (pin "TP") (pinfunction "TP_TP") (pintype "input"))
    )
    (net (code "13") (name "ENV_OUT") (class "Default")
      (node (ref "IC5") (pin "13") (pinfunction "-IN_13") (pintype "input"))
      (node (ref "IC5") (pin "14") (pinfunction "OUT_14") (pintype "output"))
      (node (ref "IC7") (pin "3") (pinfunction "IN-_3") (pintype "input"))
      (node (ref "R2") (pin "1") (pinfunction "1_1") (pintype "passive"))
      (node (ref "X1") (pin "11") (pinfunction "1_11") (pintype "passive"))
    )
    (net (code "14") (name "ENV_OUT_INV") (class "Default")
      (node (ref "IC3") (pin "14") (pinfunction "OUT_14") (pintype "output"))
      (node (ref "R1") (pin "2") (pinfunction "2_2") (pintype "passive"))
      (node (ref "X1") (pin "12") (pinfunction "1_12") (pintype "passive"))
    )
    (net (code "15") (name "EXPO_OUT") (class "Default")
      (node (ref "C30") (pin "2") (pinfunction "2_2") (pintype "passive"))
      (node (ref "IC4") (pin "14") (pinfunction "OUT_14") (pintype "output"))
      (node (ref "R87") (pin "2") (pinfunction "2_2") (pintype "passive"))
      (node (ref "R9") (pin "1") (pinfunction "1_1") (pintype "passive"))
    )
    (net (code "16") (name "EXP_REF") (class "Default")
      (node (ref "IC3") (pin "7") (pinfunction "OUT_7") (pintype "output"))
      (node (ref "R31") (pin "2") (pinfunction "2_2") (pintype "passive"))
      (node (ref "R50") (pin "1") (pinfunction "1_1") (pintype "passive"))
      (node (ref "R51") (pin "1") (pinfunction "1_1") (pintype "passive"))
    )
    (net (code "17") (name "GATE") (class "Default")
      (node (ref "C35") (pin "1") (pinfunction "1_1") (pintype "passive"))
      (node (ref "IC12") (pin "10") (pinfunction "O_10") (pintype "output"))
      (node (ref "R25") (pin "1") (pinfunction "1_1") (pintype "passive"))
    )
    (net (code "18") (name "GATE_IN") (class "Default")
      (node (ref "R27") (pin "1") (pinfunction "1_1") (pintype "passive"))
      (node (ref "R41") (pin "1") (pinfunction "1_1") (pintype "passive"))
      (node (ref "X1") (pin "5") (pinfunction "1_5") (pintype "passive"))
    )
    (net (code "19") (name "GND") (class "Default")
      (node (ref "C1") (pin "1") (pinfunction "1_1") (pintype "passive"))
      (node (ref "C10") (pin "2") (pinfunction "2_2") (pintype "passive"))
      (node (ref "C11") (pin "2") (pinfunction "2_2") (pintype "passive"))
      (node (ref "C12") (pin "2") (pinfunction "2_2") (pintype "passive"))
      (node (ref "C13") (pin "1") (pinfunction "1_1") (pintype "passive"))
      (node (ref "C14") (pin "1") (pinfunction "1_1") (pintype "passive"))
      (node (ref "C15") (pin "2") (pinfunction "2_2") (pintype "passive"))
      (node (ref "C16") (pin "1") (pinfunction "1_1") (pintype "passive"))
      (node (ref "C17") (pin "2") (pinfunction "2_2") (pintype "passive"))
      (node (ref "C18") (pin "2") (pinfunction "2_2") (pintype "passive"))
      (node (ref "C19") (pin "2") (pinfunction "2_2") (pintype "passive"))
      (node (ref "C2") (pin "2") (pinfunction "2_2") (pintype "passive"))
      (node (ref "C20") (pin "2") (pinfunction "2_2") (pintype "passive"))
      (node (ref "C21") (pin "1") (pinfunction "1_1") (pintype "passive"))
      (node (ref "C22") (pin "2") (pinfunction "2_2") (pintype "passive"))
      (node (ref "C23") (pin "-") (pinfunction "-_-") (pintype "passive"))
      (node (ref "C24") (pin "+") (pinfunction "+_+") (pintype "passive"))
      (node (ref "C29") (pin "2") (pinfunction "2_2") (pintype "passive"))
      (node (ref "C3") (pin "1") (pinfunction "1_1") (pintype "passive"))
      (node (ref "C31") (pin "2") (pinfunction "2_2") (pintype "passive"))
      (node (ref "C4") (pin "2") (pinfunction "2_2") (pintype "passive"))
      (node (ref "C5") (pin "2") (pinfunction "2_2") (pintype "passive"))
      (node (ref "C6") (pin "1") (pinfunction "1_1") (pintype "passive"))
      (node (ref "C7") (pin "2") (pinfunction "2_2") (pintype "passive"))
      (node (ref "C8") (pin "1") (pinfunction "1_1") (pintype "passive"))
      (node (ref "C9") (pin "1") (pinfunction "1_1") (pintype "passive"))
      (node (ref "IC1") (pin "10") (pinfunction "+IN_10") (pintype "input"))
      (node (ref "IC1") (pin "12") (pinfunction "+IN_12") (pintype "input"))
      (node (ref "IC1") (pin "3") (pinfunction "+IN_3") (pintype "input"))
      (node (ref "IC1") (pin "5") (pinfunction "+IN_5") (pintype "input"))
      (node (ref "IC10") (pin "1") (pinfunction "C_1") (pintype "passive"))
      (node (ref "IC11") (pin "6") (pinfunction "A_6") (pintype "passive"))
      (node (ref "IC12") (pin "7") (pinfunction "GND_7") (pintype "power_in"))
      (node (ref "IC13") (pin "7") (pinfunction "GND_7") (pintype "power_in"))
      (node (ref "IC14") (pin "14") (pinfunction "S_14") (pintype "input"))
      (node (ref "IC14") (pin "15") (pinfunction "R_15") (pintype "input"))
      (node (ref "IC14") (pin "3") (pinfunction "R_3") (pintype "input"))
      (node (ref "IC14") (pin "4") (pinfunction "S_4") (pintype "input"))
      (node (ref "IC14") (pin "8") (pinfunction "VSS_8") (pintype "power_in"))
      (node (ref "IC15") (pin "4") (pinfunction "+TR_4") (pintype "input"))
      (node (ref "IC15") (pin "8") (pinfunction "VSS_8") (pintype "power_in"))
      (node (ref "IC2") (pin "10") (pinfunction "+IN_10") (pintype "input"))
      (node (ref "IC2") (pin "12") (pinfunction "+IN_12") (pintype "input"))
      (node (ref "IC2") (pin "3") (pinfunction "+IN_3") (pintype "input"))
      (node (ref "IC2") (pin "5") (pinfunction "+IN_5") (pintype "input"))
      (node (ref "IC3") (pin "10") (pinfunction "+IN_10") (pintype "input"))
      (node (ref "IC3") (pin "3") (pinfunction "+IN_3") (pintype "input"))
      (node (ref "IC3") (pin "5") (pinfunction "+IN_5") (pintype "input"))
      (node (ref "IC4") (pin "10") (pinfunction "+IN_10") (pintype "input"))
      (node (ref "IC4") (pin "12") (pinfunction "+IN_12") (pintype "input"))
      (node (ref "IC4") (pin "3") (pinfunction "+IN_3") (pintype "input"))
      (node (ref "IC4") (pin "5") (pinfunction "+IN_5") (pintype "input"))
      (node (ref "IC5") (pin "3") (pinfunction "+IN_3") (pintype "input"))
      (node (ref "IC7") (pin "1") (pinfunction "EMIT_OUT_1") (pintype "bidirectional"))
      (node (ref "IC8") (pin "1") (pinfunction "EMIT_OUT_1") (pintype "bidirectional"))
      (node (ref "IC9") (pin "11") (pinfunction "S_11") (pintype "bidirectional"))
      (node (ref "IC9") (pin "5") (pinfunction "GND_5") (pintype "power_in"))
      (node (ref "LED1") (pin "K") (pinfunction "C_K") (pintype "passive"))
      (node (ref "LED2") (pin "K") (pinfunction "C_K") (pintype "passive"))
      (node (ref "LED3") (pin "K") (pinfunction "C_K") (pintype "passive"))
      (node (ref "LED4") (pin "K") (pinfunction "C_K") (pintype "passive"))
      (node (ref "Q3") (pin "2") (pinfunction "S_2") (pintype "passive"))
      (node (ref "Q7") (pin "2") (pinfunction "B_2") (pintype "passive"))
      (node (ref "Q8") (pin "2") (pinfunction "B_2") (pintype "passive"))
      (node (ref "Q9") (pin "2") (pinfunction "B_2") (pintype "passive"))
      (node (ref "R11") (pin "1") (pinfunction "1_1") (pintype "passive"))
      (node (ref "R14") (pin "1") (pinfunction "1_1") (pintype "passive"))
      (node (ref "R16") (pin "1") (pinfunction "1_1") (pintype "passive"))
      (node (ref "R21") (pin "1") (pinfunction "1_1") (pintype "passive"))
      (node (ref "R28") (pin "1") (pinfunction "1_1") (pintype "passive"))
      (node (ref "R41") (pin "2") (pinfunction "2_2") (pintype "passive"))
      (node (ref "R46") (pin "2") (pinfunction "2_2") (pintype "passive"))
      (node (ref "R63") (pin "1") (pinfunction "1_1") (pintype "passive"))
      (node (ref "R66") (pin "1") (pinfunction "1_1") (pintype "passive"))
      (node (ref "R67") (pin "1") (pinfunction "1_1") (pintype "passive"))
      (node (ref "R68") (pin "1") (pinfunction "1_1") (pintype "passive"))
      (node (ref "R7") (pin "2") (pinfunction "2_2") (pintype "passive"))
      (node (ref "R86") (pin "2") (pinfunction "2_2") (pintype "passive"))
      (node (ref "RV1") (pin "3") (pinfunction "E_3") (pintype "passive"))
      (node (ref "RV2") (pin "3") (pinfunction "E_3") (pintype "passive"))
      (node (ref "RV3") (pin "3") (pinfunction "E_3") (pintype "passive"))
      (node (ref "RV4") (pin "3") (pinfunction "E_3") (pintype "passive"))
      (node (ref "RV5") (pin "2") (pinfunction "S_2") (pintype "passive"))
      (node (ref "SV1") (pin "3") (pinfunction "3_3") (pintype "passive"))
      (node (ref "SV1") (pin "4") (pinfunction "4_4") (pintype "passive"))
      (node (ref "SV1") (pin "5") (pinfunction "5_5") (pintype "passive"))
      (node (ref "SV1") (pin "6") (pinfunction "6_6") (pintype "passive"))
      (node (ref "SV1") (pin "7") (pinfunction "7_7") (pintype "passive"))
      (node (ref "SV1") (pin "8") (pinfunction "8_8") (pintype "passive"))
      (node (ref "TP1") (pin "TP") (pinfunction "TP_TP") (pintype "input"))
      (node (ref "X1") (pin "7") (pinfunction "1_7") (pintype "passive"))
    )
    (net (code "20") (name "H_CV_IN") (class "Default")
      (node (ref "R40") (pin "1") (pinfunction "1_1") (pintype "passive"))
      (node (ref "X1") (pin "2") (pinfunction "1_2") (pintype "passive"))
    )
    (net (code "21") (name "H_TIMER_Q") (class "Default")
      (node (ref "IC15") (pin "6") (pinfunction "Q_6") (pintype "output"))
      (node (ref "R34") (pin "1") (pinfunction "1_1") (pintype "passive"))
      (node (ref "R61") (pin "1") (pinfunction "1_1") (pintype "passive"))
    )
    (net (code "22") (name "H_TIMER_RC") (class "Default")
      (node (ref "C37") (pin "2") (pinfunction "2_2") (pintype "passive"))
      (node (ref "IC15") (pin "2") (pinfunction "R/C_2") (pintype "input"))
      (node (ref "R30") (pin "1") (pinfunction "1_1") (pintype "passive"))
    )
    (net (code "23") (name "H_V") (class "Default")
      (node (ref "IC1") (pin "8") (pinfunction "OUT_8") (pintype "output"))
      (node (ref "R17") (pin "1") (pinfunction "1_1") (pintype "passive"))
      (node (ref "R53") (pin "2") (pinfunction "2_2") (pintype "passive"))
    )
    (net (code "24") (name "INT_IN") (class "Default")
      (node (ref "IC5") (pin "7") (pinfunction "OUT_7") (pintype "output"))
      (node (ref "R5") (pin "2") (pinfunction "2_2") (pintype "passive"))
      (node (ref "R85") (pin "1") (pinfunction "1_1") (pintype "passive"))
      (node (ref "SW2") (pin "2") (pinfunction "PR_2") (pintype "passive"))
    )
    (net (code "25") (name "I_ABC") (class "Default")
      (node (ref "IC6") (pin "16") (pinfunction "AMP/BIAS_16") (pintype "passive"))
      (node (ref "R65") (pin "2") (pinfunction "2_2") (pintype "passive"))
    )
    (net (code "26") (name "LT_0V") (class "Default")
      (node (ref "IC12") (pin "1") (pinfunction "I0_1") (pintype "input"))
      (node (ref "IC12") (pin "2") (pinfunction "I1_2") (pintype "input"))
      (node (ref "IC15") (pin "12") (pinfunction "+TR_12") (pintype "input"))
      (node (ref "IC7") (pin "7") (pinfunction "COL_OUT_7") (pintype "bidirectional"))
      (node (ref "R13") (pin "1") (pinfunction "1_1") (pintype "passive"))
      (node (ref "R42") (pin "2") (pinfunction "2_2") (pintype "passive"))
    )
    (net (code "27") (name "LT_VREF") (class "Default")
      (node (ref "C31") (pin "1") (pinfunction "1_1") (pintype "passive"))
      (node (ref "D8") (pin "C") (pinfunction "C_C") (pintype "passive"))
      (node (ref "IC12") (pin "5") (pinfunction "I1_5") (pintype "input"))
      (node (ref "IC15") (pin "5") (pinfunction "-TR_5") (pintype "input"))
      (node (ref "IC8") (pin "7") (pinfunction "COL_OUT_7") (pintype "bidirectional"))
      (node (ref "R12") (pin "1") (pinfunction "1_1") (pintype "passive"))
    )
    (net (code "28") (name "MULT_OUT") (class "Default")
      (node (ref "C26") (pin "2") (pinfunction "2_2") (pintype "passive"))
      (node (ref "IC4") (pin "8") (pinfunction "OUT_8") (pintype "output"))
      (node (ref "R3") (pin "1") (pinfunction "1_1") (pintype "passive"))
      (node (ref "R4") (pin "1") (pinfunction "1_1") (pintype "passive"))
      (node (ref "R84") (pin "2") (pinfunction "2_2") (pintype "passive"))
      (node (ref "TP3") (pin "TP") (pinfunction "TP_TP") (pintype "input"))
    )
    (net (code "29") (name "Net-(C35-Pad2)") (class "Default")
      (node (ref "C35") (pin "2") (pinfunction "2_2") (pintype "passive"))
      (node (ref "D4") (pin "A") (pinfunction "A_A") (pintype "passive"))
      (node (ref "R11") (pin "2") (pinfunction "2_2") (pintype "passive"))
    )
    (net (code "30") (name "Net-(C36-Pad2)") (class "Default")
      (node (ref "C36") (pin "2") (pinfunction "2_2") (pintype "passive"))
      (node (ref "D5") (pin "A") (pinfunction "A_A") (pintype "passive"))
      (node (ref "R21") (pin "2") (pinfunction "2_2") (pintype "passive"))
    )
    (net (code "31") (name "Net-(D1-PadA)") (class "Default")
      (node (ref "D1") (pin "A") (pinfunction "A_A") (pintype "passive"))
      (node (ref "SV1") (pin "10") (pinfunction "10_10") (pintype "passive"))
      (node (ref "SV1") (pin "9") (pinfunction "9_9") (pintype "passive"))
    )
    (net (code "32") (name "Net-(D2-PadC)") (class "Default")
      (node (ref "D2") (pin "C") (pinfunction "C_C") (pintype "passive"))
      (node (ref "SV1") (pin "1") (pinfunction "1_1") (pintype "passive"))
      (node (ref "SV1") (pin "2") (pinfunction "2_2") (pintype "passive"))
    )
    (net (code "33") (name "Net-(D7-PadA)") (class "Default")
      (node (ref "D7") (pin "A") (pinfunction "A_A") (pintype "passive"))
      (node (ref "D8") (pin "A") (pinfunction "A_A") (pintype "passive"))
      (node (ref "D9") (pin "A") (pinfunction "A_A") (pintype "passive"))
      (node (ref "LED1") (pin "A") (pinfunction "A_A") (pintype "passive"))
      (node (ref "R60") (pin "2") (pinfunction "2_2") (pintype "passive"))
    )
    (net (code "34") (name "Net-(IC1A--IN)") (class "Default")
      (node (ref "C32") (pin "1") (pinfunction "1_1") (pintype "passive"))
      (node (ref "IC1") (pin "2") (pinfunction "-IN_2") (pintype "input"))
      (node (ref "Q7") (pin "6") (pinfunction "C_6") (pintype "passive"))
      (node (ref "R51") (pin "2") (pinfunction "2_2") (pintype "passive"))
    )
    (net (code "35") (name "Net-(IC1A-OUT)") (class "Default")
      (node (ref "C32") (pin "2") (pinfunction "2_2") (pintype "passive"))
      (node (ref "IC1") (pin "1") (pinfunction "OUT_1") (pintype "output"))
      (node (ref "R74") (pin "1") (pinfunction "1_1") (pintype "passive"))
    )
    (net (code "36") (name "Net-(IC1B--IN)") (class "Default")
      (node (ref "IC1") (pin "6") (pinfunction "-IN_6") (pintype "input"))
      (node (ref "R47") (pin "2") (pinfunction "2_2") (pintype "passive"))
      (node (ref "R48") (pin "2") (pinfunction "2_2") (pintype "passive"))
      (node (ref "R54") (pin "1") (pinfunction "1_1") (pintype "passive"))
    )
    (net (code "37") (name "Net-(IC1C--IN)") (class "Default")
      (node (ref "IC1") (pin "9") (pinfunction "-IN_9") (pintype "input"))
      (node (ref "R39") (pin "2") (pinfunction "2_2") (pintype "passive"))
      (node (ref "R40") (pin "2") (pinfunction "2_2") (pintype "passive"))
      (node (ref "R53") (pin "1") (pinfunction "1_1") (pintype "passive"))
    )
    (net (code "38") (name "Net-(IC1D--IN)") (class "Default")
      (node (ref "IC1") (pin "13") (pinfunction "-IN_13") (pintype "input"))
      (node (ref "R17") (pin "2") (pinfunction "2_2") (pintype "passive"))
      (node (ref "R22") (pin "1") (pinfunction "1_1") (pintype "passive"))
      (node (ref "R75") (pin "2") (pinfunction "2_2") (pintype "passive"))
    )
    (net (code "39") (name "Net-(IC1D-OUT)") (class "Default")
      (node (ref "IC1") (pin "14") (pinfunction "OUT_14") (pintype "output"))
      (node (ref "R22") (pin "2") (pinfunction "2_2") (pintype "passive"))
      (node (ref "R81") (pin "1") (pinfunction "1_1") (pintype "passive"))
    )
    (net (code "40") (name "Net-(IC2A--IN)") (class "Default")
      (node (ref "C33") (pin "1") (pinfunction "1_1") (pintype "passive"))
      (node (ref "IC2") (pin "2") (pinfunction "-IN_2") (pintype "input"))
      (node (ref "Q9") (pin "6") (pinfunction "C_6") (pintype "passive"))
      (node (ref "R50") (pin "2") (pinfunction "2_2") (pintype "passive"))
    )
    (net (code "41") (name "Net-(IC2A-OUT)") (class "Default")
      (node (ref "C33") (pin "2") (pinfunction "2_2") (pintype "passive"))
      (node (ref "IC2") (pin "1") (pinfunction "OUT_1") (pintype "output"))
      (node (ref "R73") (pin "1") (pinfunction "1_1") (pintype "passive"))
    )
    (net (code "42") (name "Net-(IC2B--IN)") (class "Default")
      (node (ref "IC2") (pin "6") (pinfunction "-IN_6") (pintype "input"))
      (node (ref "R35") (pin "2") (pinfunction "2_2") (pintype "passive"))
      (node (ref "R49") (pin "2") (pinfunction "2_2") (pintype "passive"))
      (node (ref "R52") (pin "1") (pinfunction "1_1") (pintype "passive"))
    )
    (net (code "43") (name "Net-(IC2C--IN)") (class "Default")
      (node (ref "IC2") (pin "9") (pinfunction "-IN_9") (pintype "input"))
      (node (ref "R44") (pin "2") (pinfunction "2_2") (pintype "passive"))
      (node (ref "R45") (pin "2") (pinfunction "2_2") (pintype "passive"))
      (node (ref "R55") (pin "1") (pinfunction "1_1") (pintype "passive"))
    )
    (net (code "44") (name "Net-(IC2D--IN)") (class "Default")
      (node (ref "IC2") (pin "13") (pinfunction "-IN_13") (pintype "input"))
      (node (ref "R23") (pin "2") (pinfunction "2_2") (pintype "passive"))
      (node (ref "R24") (pin "1") (pinfunction "1_1") (pintype "passive"))
      (node (ref "R76") (pin "2") (pinfunction "2_2") (pintype "passive"))
    )
    (net (code "45") (name "Net-(IC2D-OUT)") (class "Default")
      (node (ref "IC2") (pin "14") (pinfunction "OUT_14") (pintype "output"))
      (node (ref "R24") (pin "2") (pinfunction "2_2") (pintype "passive"))
      (node (ref "R80") (pin "1") (pinfunction "1_1") (pintype "passive"))
    )
    (net (code "46") (name "Net-(IC3A--IN)") (class "Default")
      (node (ref "IC3") (pin "2") (pinfunction "-IN_2") (pintype "input"))
      (node (ref "R37") (pin "2") (pinfunction "2_2") (pintype "passive"))
      (node (ref "R38") (pin "1") (pinfunction "1_1") (pintype "passive"))
    )
    (net (code "47") (name "Net-(IC3B--IN)") (class "Default")
      (node (ref "IC3") (pin "6") (pinfunction "-IN_6") (pintype "input"))
      (node (ref "R31") (pin "1") (pinfunction "1_1") (pintype "passive"))
      (node (ref "R43") (pin "2") (pinfunction "2_2") (pintype "passive"))
      (node (ref "R77") (pin "2") (pinfunction "2_2") (pintype "passive"))
      (node (ref "R79") (pin "2") (pinfunction "2_2") (pintype "passive"))
    )
    (net (code "48") (name "Net-(IC3C--IN)") (class "Default")
      (node (ref "IC3") (pin "9") (pinfunction "-IN_9") (pintype "input"))
      (node (ref "Q4") (pin "2") (pinfunction "E_2") (pintype "passive"))
      (node (ref "R58") (pin "2") (pinfunction "2_2") (pintype "passive"))
      (node (ref "R71") (pin "1") (pinfunction "1_1") (pintype "passive"))
    )
    (net (code "49") (name "Net-(IC3C-OUT)") (class "Default")
      (node (ref "IC3") (pin "8") (pinfunction "OUT_8") (pintype "output"))
      (node (ref "Q4") (pin "1") (pinfunction "B_1") (pintype "passive"))
    )
    (net (code "50") (name "Net-(IC3D-+IN)") (class "Default")
      (node (ref "IC3") (pin "12") (pinfunction "+IN_12") (pintype "input"))
      (node (ref "R6") (pin "2") (pinfunction "2_2") (pintype "passive"))
      (node (ref "R7") (pin "1") (pinfunction "1_1") (pintype "passive"))
    )
    (net (code "51") (name "Net-(IC3D--IN)") (class "Default")
      (node (ref "IC3") (pin "13") (pinfunction "-IN_13") (pintype "input"))
      (node (ref "R1") (pin "1") (pinfunction "1_1") (pintype "passive"))
      (node (ref "R2") (pin "2") (pinfunction "2_2") (pintype "passive"))
    )
    (net (code "52") (name "Net-(IC4A--IN)") (class "Default")
      (node (ref "C28") (pin "1") (pinfunction "1_1") (pintype "passive"))
      (node (ref "IC4") (pin "2") (pinfunction "-IN_2") (pintype "input"))
      (node (ref "Q8") (pin "6") (pinfunction "C_6") (pintype "passive"))
      (node (ref "R57") (pin "2") (pinfunction "2_2") (pintype "passive"))
    )
    (net (code "53") (name "Net-(IC4A-OUT)") (class "Default")
      (node (ref "C28") (pin "2") (pinfunction "2_2") (pintype "passive"))
      (node (ref "IC4") (pin "1") (pinfunction "OUT_1") (pintype "output"))
      (node (ref "R72") (pin "1") (pinfunction "1_1") (pintype "passive"))
    )
    (net (code "54") (name "Net-(IC4B--IN)") (class "Default")
      (node (ref "C27") (pin "1") (pinfunction "1_1") (pintype "passive"))
      (node (ref "IC4") (pin "6") (pinfunction "-IN_6") (pintype "input"))
      (node (ref "Q1") (pin "2") (pinfunction "S_2") (pintype "passive"))
      (node (ref "Q2") (pin "2") (pinfunction "S_2") (pintype "passive"))
      (node (ref "R20") (pin "1") (pinfunction "1_1") (pintype "passive"))
      (node (ref "R56") (pin "2") (pinfunction "2_2") (pintype "passive"))
    )
    (net (code "55") (name "Net-(IC4B-OUT)") (class "Default")
      (node (ref "C27") (pin "2") (pinfunction "2_2") (pintype "passive"))
      (node (ref "IC4") (pin "7") (pinfunction "OUT_7") (pintype "output"))
      (node (ref "R20") (pin "2") (pinfunction "2_2") (pintype "passive"))
      (node (ref "R82") (pin "1") (pinfunction "1_1") (pintype "passive"))
    )
    (net (code "56") (name "Net-(IC4C--IN)") (class "Default")
      (node (ref "C26") (pin "1") (pinfunction "1_1") (pintype "passive"))
      (node (ref "IC4") (pin "9") (pinfunction "-IN_9") (pintype "input"))
      (node (ref "IC6") (pin "12") (pinfunction "OUT_12") (pintype "output"))
      (node (ref "R84") (pin "1") (pinfunction "1_1") (pintype "passive"))
    )
    (net (code "57") (name "Net-(IC4D--IN)") (class "Default")
      (node (ref "C30") (pin "1") (pinfunction "1_1") (pintype "passive"))
      (node (ref "IC4") (pin "13") (pinfunction "-IN_13") (pintype "input"))
      (node (ref "Q8") (pin "3") (pinfunction "C_3") (pintype "passive"))
      (node (ref "R87") (pin "1") (pinfunction "1_1") (pintype "passive"))
    )
    (net (code "58") (name "Net-(IC5A--IN)") (class "Default")
      (node (ref "C25") (pin "1") (pinfunction "1_1") (pintype "passive"))
      (node (ref "IC5") (pin "2") (pinfunction "-IN_2") (pintype "input"))
      (node (ref "IC9") (pin "14") (pinfunction "S_14") (pintype "bidirectional"))
      (node (ref "R36") (pin "2") (pinfunction "2_2") (pintype "passive"))
      (node (ref "R70") (pin "2") (pinfunction "2_2") (pintype "passive"))
      (node (ref "R85") (pin "2") (pinfunction "2_2") (pintype "passive"))
    )
    (net (code "59") (name "Net-(IC5A-OUT)") (class "Default")
      (node (ref "C34") (pin "1") (pinfunction "1_1") (pintype "passive"))
      (node (ref "IC5") (pin "1") (pinfunction "OUT_1") (pintype "output"))
      (node (ref "R69") (pin "1") (pinfunction "1_1") (pintype "passive"))
    )
    (net (code "60") (name "Net-(IC5B-+IN)") (class "Default")
      (node (ref "IC5") (pin "5") (pinfunction "+IN_5") (pintype "input"))
      (node (ref "IC9") (pin "10") (pinfunction "D_10") (pintype "bidirectional"))
      (node (ref "R4") (pin "2") (pinfunction "2_2") (pintype "passive"))
    )
    (net (code "61") (name "Net-(IC5B--IN)") (class "Default")
      (node (ref "IC5") (pin "6") (pinfunction "-IN_6") (pintype "input"))
      (node (ref "R3") (pin "2") (pinfunction "2_2") (pintype "passive"))
      (node (ref "R5") (pin "1") (pinfunction "1_1") (pintype "passive"))
    )
    (net (code "62") (name "Net-(IC5C-OUT)") (class "Default")
      (node (ref "D3") (pin "C") (pinfunction "C_C") (pintype "passive"))
      (node (ref "IC5") (pin "8") (pinfunction "OUT_8") (pintype "output"))
      (node (ref "IC8") (pin "2") (pinfunction "IN+_2") (pintype "input"))
    )
    (net (code "63") (name "Net-(IC6A-BUFF{slash}IN)") (class "Default")
      (node (ref "IC6") (pin "7") (pinfunction "BUFF/IN_7") (pintype "input"))
      (node (ref "IC6") (pin "8") (pinfunction "BUFF/OUT_8") (pintype "output"))
    )
    (net (code "64") (name "Net-(IC6B-+IN)") (class "Default")
      (node (ref "IC6") (pin "14") (pinfunction "+IN_14") (pintype "input"))
      (node (ref "RV5") (pin "3") (pinfunction "E_3") (pintype "passive"))
    )
    (net (code "65") (name "Net-(IC6B--IN)") (class "Default")
      (node (ref "IC6") (pin "13") (pinfunction "-IN_13") (pintype "input"))
      (node (ref "R9") (pin "2") (pinfunction "2_2") (pintype "passive"))
      (node (ref "RV5") (pin "1") (pinfunction "A_1") (pintype "passive"))
    )
    (net (code "66") (name "Net-(IC6B-BUFF{slash}IN)") (class "Default")
      (node (ref "IC6") (pin "10") (pinfunction "BUFF/IN_10") (pintype "input"))
      (node (ref "IC6") (pin "9") (pinfunction "BUFF/OUT_9") (pintype "output"))
    )
    (net (code "67") (name "Net-(IC6B-DIODE{slash}BIAS)") (class "Default")
      (node (ref "IC6") (pin "15") (pinfunction "DIODE/BIAS_15") (pintype "passive"))
      (node (ref "R88") (pin "2") (pinfunction "2_2") (pintype "passive"))
    )
    (net (code "68") (name "Net-(IC7-IN+)") (class "Default")
      (node (ref "IC7") (pin "2") (pinfunction "IN+_2") (pintype "input"))
      (node (ref "R28") (pin "2") (pinfunction "2_2") (pintype "passive"))
      (node (ref "R42") (pin "1") (pinfunction "1_1") (pintype "passive"))
      (node (ref "R83") (pin "2") (pinfunction "2_2") (pintype "passive"))
    )
    (net (code "69") (name "Net-(IC8-IN-)") (class "Default")
      (node (ref "D6") (pin "C") (pinfunction "C_C") (pintype "passive"))
      (node (ref "IC8") (pin "3") (pinfunction "IN-_3") (pintype "input"))
      (node (ref "R16") (pin "2") (pinfunction "2_2") (pintype "passive"))
    )
    (net (code "70") (name "Net-(IC9A-S)") (class "Default")
      (node (ref "IC9") (pin "3") (pinfunction "S_3") (pintype "bidirectional"))
      (node (ref "IC9") (pin "6") (pinfunction "S_6") (pintype "bidirectional"))
      (node (ref "R58") (pin "1") (pinfunction "1_1") (pintype "passive"))
    )
    (net (code "71") (name "Net-(IC10-R)") (class "Default")
      (node (ref "IC10") (pin "3") (pinfunction "R_3") (pintype "passive"))
      (node (ref "R8") (pin "2") (pinfunction "2_2") (pintype "passive"))
      (node (ref "R86") (pin "1") (pinfunction "1_1") (pintype "passive"))
    )
    (net (code "72") (name "Net-(IC11-R)") (class "Default")
      (node (ref "IC11") (pin "3") (pinfunction "R_3") (pintype "passive"))
      (node (ref "R63") (pin "2") (pinfunction "2_2") (pintype "passive"))
      (node (ref "R64") (pin "1") (pinfunction "1_1") (pintype "passive"))
    )
    (net (code "73") (name "Net-(IC12A-O)") (class "Default")
      (node (ref "IC12") (pin "3") (pinfunction "O_3") (pintype "output"))
      (node (ref "IC13") (pin "13") (pinfunction "I0_13") (pintype "input"))
    )
    (net (code "74") (name "Net-(IC12B-I0)") (class "Default")
      (node (ref "IC12") (pin "6") (pinfunction "I0_6") (pintype "input"))
      (node (ref "R26") (pin "2") (pinfunction "2_2") (pintype "passive"))
    )
    (net (code "75") (name "Net-(IC12C-I0)") (class "Default")
      (node (ref "IC12") (pin "8") (pinfunction "I0_8") (pintype "input"))
      (node (ref "IC12") (pin "9") (pinfunction "I1_9") (pintype "input"))
      (node (ref "Q3") (pin "3") (pinfunction "D_3") (pintype "passive"))
      (node (ref "R10") (pin "1") (pinfunction "1_1") (pintype "passive"))
    )
    (net (code "76") (name "Net-(IC13A-I0)") (class "Default")
      (node (ref "IC13") (pin "1") (pinfunction "I0_1") (pintype "input"))
      (node (ref "IC13") (pin "2") (pinfunction "I1_2") (pintype "input"))
      (node (ref "IC13") (pin "4") (pinfunction "O_4") (pintype "output"))
    )
    (net (code "77") (name "Net-(IC13A-O)") (class "Default")
      (node (ref "IC13") (pin "3") (pinfunction "O_3") (pintype "output"))
      (node (ref "IC14") (pin "7") (pinfunction "R_7") (pintype "input"))
    )
    (net (code "78") (name "Net-(IC13B-I1)") (class "Default")
      (node (ref "IC13") (pin "11") (pinfunction "O_11") (pintype "output"))
      (node (ref "IC13") (pin "5") (pinfunction "I1_5") (pintype "input"))
      (node (ref "IC14") (pin "11") (pinfunction "R_11") (pintype "input"))
    )
    (net (code "79") (name "Net-(IC15A-C)") (class "Default")
      (node (ref "C37") (pin "1") (pinfunction "1_1") (pintype "passive"))
      (node (ref "IC15") (pin "1") (pinfunction "C_1") (pintype "input"))
    )
    (net (code "80") (name "Net-(IC15B-C)") (class "Default")
      (node (ref "C38") (pin "1") (pinfunction "1_1") (pintype "passive"))
      (node (ref "IC15") (pin "15") (pinfunction "C_15") (pintype "input"))
    )
    (net (code "81") (name "Net-(LED2-PadA)") (class "Default")
      (node (ref "LED2") (pin "A") (pinfunction "A_A") (pintype "passive"))
      (node (ref "R61") (pin "2") (pinfunction "2_2") (pintype "passive"))
    )
    (net (code "82") (name "Net-(LED3-PadA)") (class "Default")
      (node (ref "LED3") (pin "A") (pinfunction "A_A") (pintype "passive"))
      (node (ref "R62") (pin "2") (pinfunction "2_2") (pintype "passive"))
    )
    (net (code "83") (name "Net-(LED4-PadA)") (class "Default")
      (node (ref "LED4") (pin "A") (pinfunction "A_A") (pintype "passive"))
      (node (ref "R59") (pin "2") (pinfunction "2_2") (pintype "passive"))
    )
    (net (code "84") (name "Net-(Q1-D)") (class "Default")
      (node (ref "Q1") (pin "3") (pinfunction "D_3") (pintype "passive"))
      (node (ref "R19") (pin "2") (pinfunction "2_2") (pintype "passive"))
    )
    (net (code "85") (name "Net-(Q2-D)") (class "Default")
      (node (ref "Q2") (pin "3") (pinfunction "D_3") (pintype "passive"))
      (node (ref "R18") (pin "2") (pinfunction "2_2") (pintype "passive"))
    )
    (net (code "86") (name "Net-(Q3-G)") (class "Default")
      (node (ref "Q3") (pin "1") (pinfunction "G_1") (pintype "passive"))
      (node (ref "R27") (pin "2") (pinfunction "2_2") (pintype "passive"))
    )
    (net (code "87") (name "Net-(Q4-C)") (class "Default")
      (node (ref "Q4") (pin "3") (pinfunction "C_3") (pintype "passive"))
      (node (ref "R65") (pin "1") (pinfunction "1_1") (pintype "passive"))
    )
    (net (code "88") (name "Net-(Q5-C)") (class "Default")
      (node (ref "Q5") (pin "3") (pinfunction "C_3") (pintype "passive"))
      (node (ref "R33") (pin "2") (pinfunction "2_2") (pintype "passive"))
    )
    (net (code "89") (name "Net-(Q6-C)") (class "Default")
      (node (ref "Q6") (pin "3") (pinfunction "C_3") (pintype "passive"))
      (node (ref "R30") (pin "2") (pinfunction "2_2") (pintype "passive"))
    )
    (net (code "90") (name "Net-(Q7A-B)") (class "Default")
      (node (ref "Q7") (pin "1") (pinfunction "B_1") (pintype "passive"))
      (node (ref "R68") (pin "2") (pinfunction "2_2") (pintype "passive"))
      (node (ref "R81") (pin "2") (pinfunction "2_2") (pintype "passive"))
    )
    (net (code "91") (name "Net-(Q7A-E)") (class "Default")
      (node (ref "Q7") (pin "4") (pinfunction "E_4") (pintype "passive"))
      (node (ref "Q7") (pin "5") (pinfunction "E_5") (pintype "passive"))
      (node (ref "R74") (pin "2") (pinfunction "2_2") (pintype "passive"))
    )
    (net (code "92") (name "Net-(Q7B-C)") (class "Default")
      (node (ref "Q7") (pin "3") (pinfunction "C_3") (pintype "passive"))
      (node (ref "R29") (pin "1") (pinfunction "1_1") (pintype "passive"))
    )
    (net (code "93") (name "Net-(Q8A-B)") (class "Default")
      (node (ref "Q8") (pin "1") (pinfunction "B_1") (pintype "passive"))
      (node (ref "R66") (pin "2") (pinfunction "2_2") (pintype "passive"))
      (node (ref "R82") (pin "2") (pinfunction "2_2") (pintype "passive"))
    )
    (net (code "94") (name "Net-(Q8A-E)") (class "Default")
      (node (ref "Q8") (pin "4") (pinfunction "E_4") (pintype "passive"))
      (node (ref "Q8") (pin "5") (pinfunction "E_5") (pintype "passive"))
      (node (ref "R72") (pin "2") (pinfunction "2_2") (pintype "passive"))
    )
    (net (code "95") (name "Net-(Q9A-B)") (class "Default")
      (node (ref "Q9") (pin "1") (pinfunction "B_1") (pintype "passive"))
      (node (ref "R67") (pin "2") (pinfunction "2_2") (pintype "passive"))
      (node (ref "R80") (pin "2") (pinfunction "2_2") (pintype "passive"))
    )
    (net (code "96") (name "Net-(Q9A-E)") (class "Default")
      (node (ref "Q9") (pin "4") (pinfunction "E_4") (pintype "passive"))
      (node (ref "Q9") (pin "5") (pinfunction "E_5") (pintype "passive"))
      (node (ref "R73") (pin "2") (pinfunction "2_2") (pintype "passive"))
    )
    (net (code "97") (name "Net-(Q9B-C)") (class "Default")
      (node (ref "Q9") (pin "3") (pinfunction "C_3") (pintype "passive"))
      (node (ref "R32") (pin "1") (pinfunction "1_1") (pintype "passive"))
    )
    (net (code "98") (name "Net-(Q10A-B)") (class "Default")
      (node (ref "Q10") (pin "1") (pinfunction "B_1") (pintype "passive"))
      (node (ref "Q10") (pin "2") (pinfunction "B_2") (pintype "passive"))
      (node (ref "Q10") (pin "3") (pinfunction "C_3") (pintype "passive"))
      (node (ref "Q5") (pin "2") (pinfunction "E_2") (pintype "passive"))
    )
    (net (code "99") (name "Net-(Q10A-C)") (class "Default")
      (node (ref "Q10") (pin "6") (pinfunction "C_6") (pintype "passive"))
      (node (ref "Q5") (pin "1") (pinfunction "B_1") (pintype "passive"))
      (node (ref "R32") (pin "2") (pinfunction "2_2") (pintype "passive"))
    )
    (net (code "100") (name "Net-(Q11A-B)") (class "Default")
      (node (ref "Q11") (pin "1") (pinfunction "B_1") (pintype "passive"))
      (node (ref "Q11") (pin "2") (pinfunction "B_2") (pintype "passive"))
      (node (ref "Q11") (pin "3") (pinfunction "C_3") (pintype "passive"))
      (node (ref "Q6") (pin "2") (pinfunction "E_2") (pintype "passive"))
    )
    (net (code "101") (name "Net-(Q11A-C)") (class "Default")
      (node (ref "Q11") (pin "6") (pinfunction "C_6") (pintype "passive"))
      (node (ref "Q6") (pin "1") (pinfunction "B_1") (pintype "passive"))
      (node (ref "R29") (pin "2") (pinfunction "2_2") (pintype "passive"))
    )
    (net (code "102") (name "Net-(RV1-S)") (class "Default")
      (node (ref "R47") (pin "1") (pinfunction "1_1") (pintype "passive"))
      (node (ref "RV1") (pin "2") (pinfunction "S_2") (pintype "passive"))
    )
    (net (code "103") (name "Net-(RV2-S)") (class "Default")
      (node (ref "R39") (pin "1") (pinfunction "1_1") (pintype "passive"))
      (node (ref "RV2") (pin "2") (pinfunction "S_2") (pintype "passive"))
    )
    (net (code "104") (name "Net-(RV3-S)") (class "Default")
      (node (ref "R49") (pin "1") (pinfunction "1_1") (pintype "passive"))
      (node (ref "RV3") (pin "2") (pinfunction "S_2") (pintype "passive"))
    )
    (net (code "105") (name "Net-(RV4-S)") (class "Default")
      (node (ref "R44") (pin "1") (pinfunction "1_1") (pintype "passive"))
      (node (ref "RV4") (pin "2") (pinfunction "S_2") (pintype "passive"))
    )
    (net (code "106") (name "Net-(RV6-S)") (class "Default")
      (node (ref "R64") (pin "2") (pinfunction "2_2") (pintype "passive"))
      (node (ref "RV6") (pin "2") (pinfunction "S_2") (pintype "passive"))
    )
    (net (code "107") (name "Net-(SW1A-LD)") (class "Default")
      (node (ref "R34") (pin "2") (pinfunction "2_2") (pintype "passive"))
      (node (ref "SW1") (pin "3") (pinfunction "LD_3") (pintype "passive"))
    )
    (net (code "108") (name "Net-(SW1A-LU)") (class "Default")
      (node (ref "R25") (pin "2") (pinfunction "2_2") (pintype "passive"))
      (node (ref "SW1") (pin "1") (pinfunction "LU_1") (pintype "passive"))
    )
    (net (code "109") (name "Net-(SW1A-PL)") (class "Default")
      (node (ref "R26") (pin "1") (pinfunction "1_1") (pintype "passive"))
      (node (ref "SW1") (pin "2") (pinfunction "PL_2") (pintype "passive"))
    )
    (net (code "110") (name "Net-(SW1A-PR)") (class "Default")
      (node (ref "C36") (pin "1") (pinfunction "1_1") (pintype "passive"))
      (node (ref "R46") (pin "1") (pinfunction "1_1") (pintype "passive"))
      (node (ref "SW1") (pin "5") (pinfunction "PR_5") (pintype "passive"))
    )
    (net (code "111") (name "Net-(SW1A-RD)") (class "Default")
      (node (ref "R78") (pin "2") (pinfunction "2_2") (pintype "passive"))
      (node (ref "SW1") (pin "6") (pinfunction "RD_6") (pintype "passive"))
    )
    (net (code "112") (name "Net-(SW2-RD)") (class "Default")
      (node (ref "R36") (pin "1") (pinfunction "1_1") (pintype "passive"))
      (node (ref "SW2") (pin "3") (pinfunction "RD_3") (pintype "passive"))
    )
    (net (code "113") (name "Net-(SW2-RU)") (class "Default")
      (node (ref "R70") (pin "1") (pinfunction "1_1") (pintype "passive"))
      (node (ref "SW2") (pin "1") (pinfunction "RU_1") (pintype "passive"))
    )
    (net (code "114") (name "Net-(SW3-RD)") (class "Default")
      (node (ref "R43") (pin "1") (pinfunction "1_1") (pintype "passive"))
      (node (ref "SW3") (pin "3") (pinfunction "RD_3") (pintype "passive"))
    )
    (net (code "115") (name "Net-(SW3-RU)") (class "Default")
      (node (ref "R79") (pin "1") (pinfunction "1_1") (pintype "passive"))
      (node (ref "SW3") (pin "1") (pinfunction "RU_1") (pintype "passive"))
    )
    (net (code "116") (name "REL_SHP") (class "Default")
      (node (ref "IC9") (pin "2") (pinfunction "D_2") (pintype "bidirectional"))
      (node (ref "X1") (pin "10") (pinfunction "1_10") (pintype "passive"))
    )
    (net (code "117") (name "REL{slash}~{ATT}") (class "Default")
      (node (ref "IC13") (pin "8") (pinfunction "I0_8") (pintype "input"))
      (node (ref "IC13") (pin "9") (pinfunction "I1_9") (pintype "input"))
      (node (ref "IC14") (pin "9") (pinfunction "Q_9") (pintype "output"))
      (node (ref "IC9") (pin "8") (pinfunction "IN_8") (pintype "input"))
      (node (ref "IC9") (pin "9") (pinfunction "IN_9") (pintype "input"))
      (node (ref "Q2") (pin "1") (pinfunction "G_1") (pintype "passive"))
      (node (ref "R62") (pin "1") (pinfunction "1_1") (pintype "passive"))
    )
    (net (code "118") (name "TRIGS") (class "Default")
      (node (ref "D4") (pin "C") (pinfunction "C_C") (pintype "passive"))
      (node (ref "D5") (pin "C") (pinfunction "C_C") (pintype "passive"))
      (node (ref "IC13") (pin "6") (pinfunction "I0_6") (pintype "input"))
      (node (ref "IC14") (pin "12") (pinfunction "S_12") (pintype "input"))
      (node (ref "R14") (pin "2") (pinfunction "2_2") (pintype "passive"))
    )
    (net (code "119") (name "VREF") (class "Default")
      (node (ref "IC11") (pin "1") (pinfunction "C_1") (pintype "passive"))
      (node (ref "IC5") (pin "10") (pinfunction "+IN_10") (pintype "input"))
      (node (ref "R6") (pin "1") (pinfunction "1_1") (pintype "passive"))
      (node (ref "R89") (pin "2") (pinfunction "2_2") (pintype "passive"))
      (node (ref "RV6") (pin "1") (pinfunction "A_1") (pintype "passive"))
      (node (ref "TP2") (pin "TP") (pinfunction "TP_TP") (pintype "input"))
    )
    (net (code "120") (name "W_CV_IN") (class "Default")
      (node (ref "R45") (pin "1") (pinfunction "1_1") (pintype "passive"))
      (node (ref "X1") (pin "4") (pinfunction "1_4") (pintype "passive"))
    )
    (net (code "121") (name "W_TIMER_Q") (class "Default")
      (node (ref "IC15") (pin "10") (pinfunction "Q_10") (pintype "output"))
      (node (ref "R59") (pin "1") (pinfunction "1_1") (pintype "passive"))
    )
    (net (code "122") (name "W_TIMER_RC") (class "Default")
      (node (ref "C38") (pin "2") (pinfunction "2_2") (pintype "passive"))
      (node (ref "IC15") (pin "14") (pinfunction "R/C_14") (pintype "input"))
      (node (ref "R33") (pin "1") (pinfunction "1_1") (pintype "passive"))
    )
    (net (code "123") (name "W_TIMER_~{Q}") (class "Default")
      (node (ref "IC15") (pin "9") (pinfunction "~{Q}_9") (pintype "output"))
      (node (ref "R78") (pin "1") (pinfunction "1_1") (pintype "passive"))
    )
    (net (code "124") (name "W_V") (class "Default")
      (node (ref "IC2") (pin "8") (pinfunction "OUT_8") (pintype "output"))
      (node (ref "R23") (pin "1") (pinfunction "1_1") (pintype "passive"))
      (node (ref "R55") (pin "2") (pinfunction "2_2") (pintype "passive"))
    )
    (net (code "125") (name "unconnected-(IC6A-+IN-Pad3)") (class "Default")
      (node (ref "IC6") (pin "3") (pinfunction "+IN_3") (pintype "input"))
    )
    (net (code "126") (name "unconnected-(IC6A--IN-Pad4)") (class "Default")
      (node (ref "IC6") (pin "4") (pinfunction "-IN_4") (pintype "input"))
    )
    (net (code "127") (name "unconnected-(IC6A-DIODE{slash}BIAS-Pad2)") (class "Default")
      (node (ref "IC6") (pin "2") (pinfunction "DIODE/BIAS_2") (pintype "passive"))
    )
    (net (code "128") (name "unconnected-(IC6A-OUT-Pad5)") (class "Default")
      (node (ref "IC6") (pin "5") (pinfunction "OUT_5") (pintype "output"))
    )
    (net (code "129") (name "unconnected-(IC7-BALANCE-Pad5)") (class "Default")
      (node (ref "IC7") (pin "5") (pinfunction "BALANCE_5") (pintype "bidirectional"))
    )
    (net (code "130") (name "unconnected-(IC7-BAL{slash}STRB-Pad6)") (class "Default")
      (node (ref "IC7") (pin "6") (pinfunction "BAL/STRB_6") (pintype "bidirectional"))
    )
    (net (code "131") (name "unconnected-(IC8-BALANCE-Pad5)") (class "Default")
      (node (ref "IC8") (pin "5") (pinfunction "BALANCE_5") (pintype "bidirectional"))
    )
    (net (code "132") (name "unconnected-(IC8-BAL{slash}STRB-Pad6)") (class "Default")
      (node (ref "IC8") (pin "6") (pinfunction "BAL/STRB_6") (pintype "bidirectional"))
    )
    (net (code "133") (name "unconnected-(IC12D-O-Pad11)") (class "Default")
      (node (ref "IC12") (pin "11") (pinfunction "O_11") (pintype "output"))
    )
    (net (code "134") (name "unconnected-(IC14A-Q-Pad2)") (class "Default")
      (node (ref "IC14") (pin "2") (pinfunction "Q_2") (pintype "output"))
    )
    (net (code "135") (name "unconnected-(IC14D-Q-Pad1)") (class "Default")
      (node (ref "IC14") (pin "1") (pinfunction "Q_1") (pintype "output"))
    )
    (net (code "136") (name "unconnected-(IC15A-~{Q}-Pad7)") (class "Default")
      (node (ref "IC15") (pin "7") (pinfunction "~{Q}_7") (pintype "output"))
    )
    (net (code "137") (name "unconnected-(RV6-E-Pad3)") (class "Default")
      (node (ref "RV6") (pin "3") (pinfunction "E_3") (pintype "passive"))
    )
    (net (code "138") (name "unconnected-(SV1-Pad11)") (class "Default")
      (node (ref "SV1") (pin "11") (pinfunction "11_11") (pintype "passive"))
    )
    (net (code "139") (name "unconnected-(SV1-Pad12)") (class "Default")
      (node (ref "SV1") (pin "12") (pinfunction "12_12") (pintype "passive"))
    )
    (net (code "140") (name "unconnected-(SV1-Pad13)") (class "Default")
      (node (ref "SV1") (pin "13") (pinfunction "13_13") (pintype "passive"))
    )
    (net (code "141") (name "unconnected-(SV1-Pad14)") (class "Default")
      (node (ref "SV1") (pin "14") (pinfunction "14_14") (pintype "passive"))
    )
    (net (code "142") (name "unconnected-(SV1-Pad15)") (class "Default")
      (node (ref "SV1") (pin "15") (pinfunction "15_15") (pintype "passive"))
    )
    (net (code "143") (name "unconnected-(SV1-Pad16)") (class "Default")
      (node (ref "SV1") (pin "16") (pinfunction "16_16") (pintype "passive"))
    )
    (net (code "144") (name "unconnected-(SW1A-RU-Pad4)") (class "Default")
      (node (ref "SW1") (pin "4") (pinfunction "RU_4") (pintype "passive"))
    )
    (net (code "145") (name "~{NET_GATE_F}") (class "Default")
      (node (ref "C29") (pin "1") (pinfunction "1_1") (pintype "passive"))
      (node (ref "IC14") (pin "6") (pinfunction "S_6") (pintype "input"))
      (node (ref "R15") (pin "2") (pinfunction "2_2") (pintype "passive"))
    )
    (net (code "146") (name "~{NET_GATE}") (class "Default")
      (node (ref "IC12") (pin "4") (pinfunction "O_4") (pintype "output"))
      (node (ref "R15") (pin "1") (pinfunction "1_1") (pintype "passive"))
    )
  )
)
